# 2022-11-10.net
KiCad netlist of a schematic drawn in EasyEDA
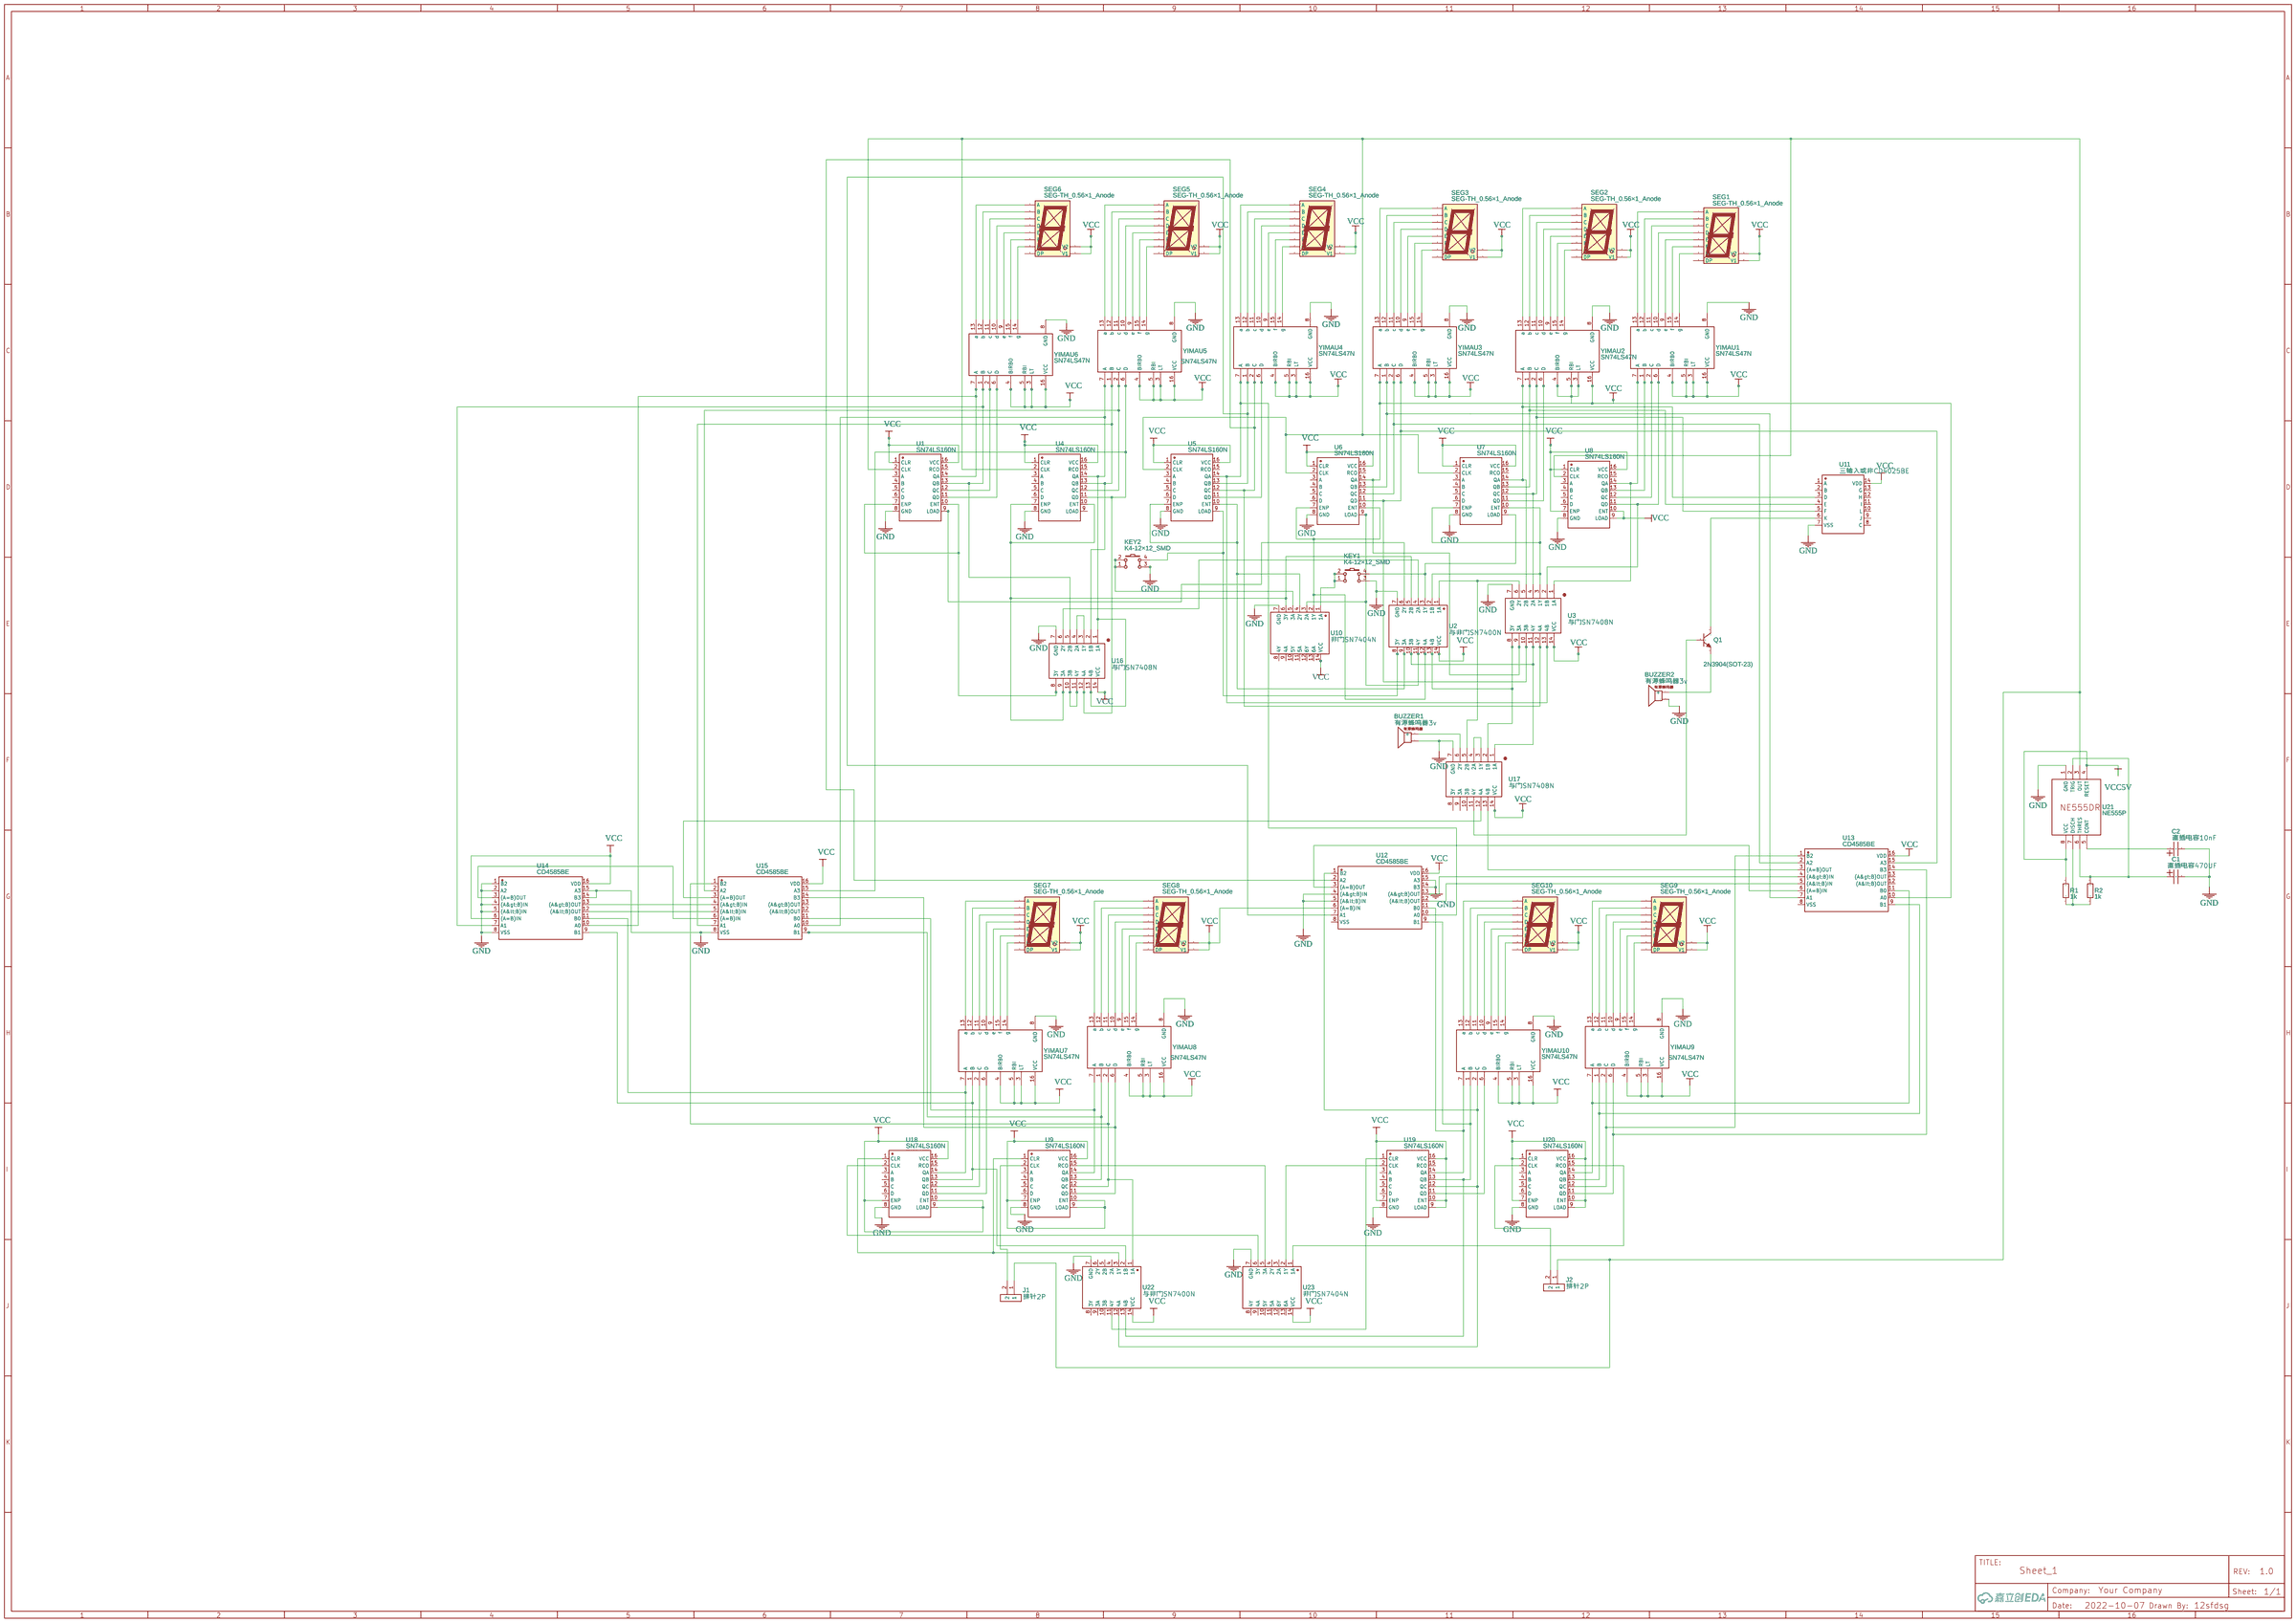
[diagram p0: schematic sheet]

(export (version "E")
  (design (tool "Eeschema 10.0.6"))
  (components
    (comp (ref "BUZZER1")
      (value "有源蜂鸣器3v")
      (fields (field (name "BOM_Manufacturer Part") "TMB12A12") (field (name "BOM_Supplier Part") "C96079"))
      (libsource (lib "") (part "有源蜂鸣器3v"))
    )
    (comp (ref "BUZZER2")
      (value "有源蜂鸣器3v")
      (fields (field (name "BOM_Manufacturer Part") "TMB12A12") (field (name "BOM_Supplier Part") "C96079"))
      (libsource (lib "") (part "有源蜂鸣器3v"))
    )
    (comp (ref "C1") (value "直插电容470UF") (libsource (lib "") (part "直插电容470UF_1")))
    (comp (ref "C2") (value "直插电容10nF") (libsource (lib "") (part "直插电容470UF")))
    (comp (ref "J1") (value "排针2P") (libsource (lib "") (part "排针2P")))
    (comp (ref "J2") (value "排针2P") (libsource (lib "") (part "排针2P")))
    (comp (ref "KEY1")
      (value "K4-12×12_SMD")
      (fields
        (field (name "BOM_Manufacturer Part") "K2-1103SP-E4SW-04")
        (field (name "BOM_Supplier Part") "C136697")
      )
      (libsource (lib "") (part "K4-12×12_SMD"))
    )
    (comp (ref "KEY2")
      (value "K4-12×12_SMD")
      (fields
        (field (name "BOM_Manufacturer Part") "K2-1103SP-E4SW-04")
        (field (name "BOM_Supplier Part") "C136697")
      )
      (libsource (lib "") (part "K4-12×12_SMD"))
    )
    (comp (ref "Q1")
      (value "2N3904(SOT-23)")
      (fields
        (field (name "BOM_Manufacturer Part") "2n3904S-RTK/PS")
        (field (name "BOM_Supplier Part") "C18536")
      )
      (libsource (lib "") (part "2N3904(SOT-23)"))
    )
    (comp (ref "R1")
      (value "1k")
      (fields
        (field (name "BOM_Manufacturer Part") "CFR0W4J0681A50")
        (field (name "BOM_Supplier Part") "C70784")
      )
      (libsource (lib "") (part "直插电阻"))
    )
    (comp (ref "R2")
      (value "1k")
      (fields
        (field (name "BOM_Manufacturer Part") "CFR0W4J0681A50")
        (field (name "BOM_Supplier Part") "C70784")
      )
      (libsource (lib "") (part "直插电阻"))
    )
    (comp (ref "SEG1")
      (value "SEG-TH_0.56×1_Anode")
      (fields (field (name "BOM_Supplier Part") "C8092"))
      (libsource (lib "") (part "SEG-TH_0.56×1_Anode"))
    )
    (comp (ref "SEG2")
      (value "SEG-TH_0.56×1_Anode")
      (fields (field (name "BOM_Supplier Part") "C8092"))
      (libsource (lib "") (part "SEG-TH_0.56×1_Anode"))
    )
    (comp (ref "SEG3")
      (value "SEG-TH_0.56×1_Anode")
      (fields (field (name "BOM_Supplier Part") "C8092"))
      (libsource (lib "") (part "SEG-TH_0.56×1_Anode"))
    )
    (comp (ref "SEG4")
      (value "SEG-TH_0.56×1_Anode")
      (fields (field (name "BOM_Supplier Part") "C8092"))
      (libsource (lib "") (part "SEG-TH_0.56×1_Anode"))
    )
    (comp (ref "SEG5")
      (value "SEG-TH_0.56×1_Anode")
      (fields (field (name "BOM_Supplier Part") "C8092"))
      (libsource (lib "") (part "SEG-TH_0.56×1_Anode"))
    )
    (comp (ref "SEG6")
      (value "SEG-TH_0.56×1_Anode")
      (fields (field (name "BOM_Supplier Part") "C8092"))
      (libsource (lib "") (part "SEG-TH_0.56×1_Anode"))
    )
    (comp (ref "SEG7")
      (value "SEG-TH_0.56×1_Anode")
      (fields (field (name "BOM_Supplier Part") "C8092"))
      (libsource (lib "") (part "SEG-TH_0.56×1_Anode"))
    )
    (comp (ref "SEG8")
      (value "SEG-TH_0.56×1_Anode")
      (fields (field (name "BOM_Supplier Part") "C8092"))
      (libsource (lib "") (part "SEG-TH_0.56×1_Anode"))
    )
    (comp (ref "SEG9")
      (value "SEG-TH_0.56×1_Anode")
      (fields (field (name "BOM_Supplier Part") "C8092"))
      (libsource (lib "") (part "SEG-TH_0.56×1_Anode"))
    )
    (comp (ref "SEG10")
      (value "SEG-TH_0.56×1_Anode")
      (fields (field (name "BOM_Supplier Part") "C8092"))
      (libsource (lib "") (part "SEG-TH_0.56×1_Anode"))
    )
    (comp (ref "U1")
      (value "SN74LS160N")
      (fields
        (field (name "BOM_Manufacturer Part") "CC0805JRNPO9BN821")
        (field (name "BOM_Supplier Part") "C113834")
      )
      (libsource (lib "") (part "SN74LS160N"))
    )
    (comp (ref "U2") (value "与非门SN7400N") (libsource (lib "") (part "SN7400N")))
    (comp (ref "U3") (value "与门SN7408N") (libsource (lib "") (part "SN7408N")))
    (comp (ref "U4")
      (value "SN74LS160N")
      (fields
        (field (name "BOM_Manufacturer Part") "CC0805JRNPO9BN821")
        (field (name "BOM_Supplier Part") "C113834")
      )
      (libsource (lib "") (part "SN74LS160N"))
    )
    (comp (ref "U5")
      (value "SN74LS160N")
      (fields
        (field (name "BOM_Manufacturer Part") "CC0805JRNPO9BN821")
        (field (name "BOM_Supplier Part") "C113834")
      )
      (libsource (lib "") (part "SN74LS160N"))
    )
    (comp (ref "U6")
      (value "SN74LS160N")
      (fields
        (field (name "BOM_Manufacturer Part") "CC0805JRNPO9BN821")
        (field (name "BOM_Supplier Part") "C113834")
      )
      (libsource (lib "") (part "SN74LS160N"))
    )
    (comp (ref "U7")
      (value "SN74LS160N")
      (fields
        (field (name "BOM_Manufacturer Part") "CC0805JRNPO9BN821")
        (field (name "BOM_Supplier Part") "C113834")
      )
      (libsource (lib "") (part "SN74LS160N"))
    )
    (comp (ref "U8")
      (value "SN74LS160N")
      (fields
        (field (name "BOM_Manufacturer Part") "CC0805JRNPO9BN821")
        (field (name "BOM_Supplier Part") "C113834")
      )
      (libsource (lib "") (part "SN74LS160N"))
    )
    (comp (ref "U9")
      (value "SN74LS160N")
      (fields
        (field (name "BOM_Manufacturer Part") "CC0805JRNPO9BN821")
        (field (name "BOM_Supplier Part") "C113834")
      )
      (libsource (lib "") (part "SN74LS160N"))
    )
    (comp (ref "U10") (value "非门SN7404N") (libsource (lib "") (part "SN7404N")))
    (comp (ref "U11")
      (value "三输入或非CD4025BE")
      (fields (field (name "BOM_Manufacturer Part") "CD4025BE") (field (name "BOM_Supplier Part") "C28214"))
      (libsource (lib "") (part "CD4025BE"))
    )
    (comp (ref "U12")
      (value "CD4585BE")
      (fields (field (name "BOM_Supplier Part") "C31466"))
      (libsource (lib "") (part "CD4585BE"))
    )
    (comp (ref "U13")
      (value "CD4585BE")
      (fields (field (name "BOM_Supplier Part") "C31466"))
      (libsource (lib "") (part "CD4585BE"))
    )
    (comp (ref "U14")
      (value "CD4585BE")
      (fields (field (name "BOM_Supplier Part") "C31466"))
      (libsource (lib "") (part "CD4585BE"))
    )
    (comp (ref "U15")
      (value "CD4585BE")
      (fields (field (name "BOM_Supplier Part") "C31466"))
      (libsource (lib "") (part "CD4585BE"))
    )
    (comp (ref "U16") (value "与门SN7408N") (libsource (lib "") (part "SN7408N")))
    (comp (ref "U17") (value "与门SN7408N") (libsource (lib "") (part "SN7408N")))
    (comp (ref "U18")
      (value "SN74LS160N")
      (fields
        (field (name "BOM_Manufacturer Part") "CC0805JRNPO9BN821")
        (field (name "BOM_Supplier Part") "C113834")
      )
      (libsource (lib "") (part "SN74LS160N"))
    )
    (comp (ref "U19")
      (value "SN74LS160N")
      (fields
        (field (name "BOM_Manufacturer Part") "CC0805JRNPO9BN821")
        (field (name "BOM_Supplier Part") "C113834")
      )
      (libsource (lib "") (part "SN74LS160N"))
    )
    (comp (ref "U20")
      (value "SN74LS160N")
      (fields
        (field (name "BOM_Manufacturer Part") "CC0805JRNPO9BN821")
        (field (name "BOM_Supplier Part") "C113834")
      )
      (libsource (lib "") (part "SN74LS160N"))
    )
    (comp (ref "U21") (value "NE555P") (libsource (lib "") (part "NE555P")))
    (comp (ref "U22") (value "与非门SN7400N") (libsource (lib "") (part "SN7400N")))
    (comp (ref "U23") (value "非门SN7404N") (libsource (lib "") (part "SN7404N")))
    (comp (ref "YIMAU1")
      (value "SN74LS47N")
      (fields (field (name "BOM_Supplier Part") "C129379"))
      (libsource (lib "") (part "Unknown_2395_-1825"))
    )
    (comp (ref "YIMAU2")
      (value "SN74LS47N")
      (fields (field (name "BOM_Supplier Part") "C129379"))
      (libsource (lib "") (part "Unknown_2230_-1820"))
    )
    (comp (ref "YIMAU3")
      (value "SN74LS47N")
      (fields (field (name "BOM_Supplier Part") "C129379"))
      (libsource (lib "") (part "Unknown_2025_-1825"))
    )
    (comp (ref "YIMAU4")
      (value "SN74LS47N")
      (fields (field (name "BOM_Supplier Part") "C129379"))
      (libsource (lib "") (part "Unknown_1825_-1825"))
    )
    (comp (ref "YIMAU5")
      (value "SN74LS47N")
      (fields (field (name "BOM_Supplier Part") "C129379"))
      (libsource (lib "") (part "Unknown_1630_-1820"))
    )
    (comp (ref "YIMAU6")
      (value "SN74LS47N")
      (fields (field (name "BOM_Supplier Part") "C129379"))
      (libsource (lib "") (part "Unknown_1445_-1815"))
    )
    (comp (ref "YIMAU7")
      (value "SN74LS47N")
      (fields (field (name "BOM_Supplier Part") "C129379"))
      (libsource (lib "") (part "Unknown_1430_-815"))
    )
    (comp (ref "YIMAU8")
      (value "SN74LS47N")
      (fields (field (name "BOM_Supplier Part") "C129379"))
      (libsource (lib "") (part "Unknown_1615_-820"))
    )
    (comp (ref "YIMAU9")
      (value "SN74LS47N")
      (fields (field (name "BOM_Supplier Part") "C129379"))
      (libsource (lib "") (part "Unknown_2330_-820"))
    )
    (comp (ref "YIMAU10")
      (value "SN74LS47N")
      (fields (field (name "BOM_Supplier Part") "C129379"))
      (libsource (lib "") (part "Unknown_2145_-815"))
    )
  )
  (nets
    (net (code "1") (name "GND") (class "Default")
      (node (ref "BUZZER1") (pin "-") (pinfunction "-_-") (pintype "unspecified"))
      (node (ref "BUZZER2") (pin "-") (pinfunction "-_-") (pintype "unspecified"))
      (node (ref "C1") (pin "2") (pinfunction "2_2") (pintype "unspecified"))
      (node (ref "C2") (pin "2") (pinfunction "2_2") (pintype "unspecified"))
      (node (ref "KEY1") (pin "3") (pinfunction "3_3") (pintype "unspecified"))
      (node (ref "KEY2") (pin "3") (pinfunction "3_3") (pintype "unspecified"))
      (node (ref "U1") (pin "8") (pinfunction "GND_8") (pintype "unspecified"))
      (node (ref "U10") (pin "7") (pinfunction "GND_7") (pintype "unspecified"))
      (node (ref "U11") (pin "7") (pinfunction "VSS_7") (pintype "unspecified"))
      (node (ref "U12") (pin "14") (pinfunction "B3_14") (pintype "unspecified"))
      (node (ref "U12") (pin "15") (pinfunction "A3_15") (pintype "unspecified"))
      (node (ref "U12") (pin "4") (pinfunction "(A&gt;B)IN_4") (pintype "unspecified"))
      (node (ref "U12") (pin "5") (pinfunction "(A&lt;B)IN_5") (pintype "unspecified"))
      (node (ref "U14") (pin "1") (pinfunction "B2_1") (pintype "unspecified"))
      (node (ref "U14") (pin "14") (pinfunction "B3_14") (pintype "unspecified"))
      (node (ref "U14") (pin "15") (pinfunction "A3_15") (pintype "unspecified"))
      (node (ref "U14") (pin "2") (pinfunction "A2_2") (pintype "unspecified"))
      (node (ref "U14") (pin "4") (pinfunction "(A&gt;B)IN_4") (pintype "unspecified"))
      (node (ref "U14") (pin "5") (pinfunction "(A&lt;B)IN_5") (pintype "unspecified"))
      (node (ref "U14") (pin "8") (pinfunction "VSS_8") (pintype "unspecified"))
      (node (ref "U15") (pin "8") (pinfunction "VSS_8") (pintype "unspecified"))
      (node (ref "U16") (pin "7") (pinfunction "GND_7") (pintype "unspecified"))
      (node (ref "U17") (pin "7") (pinfunction "GND_7") (pintype "unspecified"))
      (node (ref "U18") (pin "8") (pinfunction "GND_8") (pintype "unspecified"))
      (node (ref "U19") (pin "8") (pinfunction "GND_8") (pintype "unspecified"))
      (node (ref "U2") (pin "7") (pinfunction "GND_7") (pintype "unspecified"))
      (node (ref "U20") (pin "8") (pinfunction "GND_8") (pintype "unspecified"))
      (node (ref "U21") (pin "1") (pinfunction "GND_1") (pintype "unspecified"))
      (node (ref "U22") (pin "7") (pinfunction "GND_7") (pintype "unspecified"))
      (node (ref "U23") (pin "7") (pinfunction "GND_7") (pintype "unspecified"))
      (node (ref "U3") (pin "7") (pinfunction "GND_7") (pintype "unspecified"))
      (node (ref "U4") (pin "8") (pinfunction "GND_8") (pintype "unspecified"))
      (node (ref "U5") (pin "8") (pinfunction "GND_8") (pintype "unspecified"))
      (node (ref "U6") (pin "8") (pinfunction "GND_8") (pintype "unspecified"))
      (node (ref "U7") (pin "8") (pinfunction "GND_8") (pintype "unspecified"))
      (node (ref "U8") (pin "8") (pinfunction "GND_8") (pintype "unspecified"))
      (node (ref "U9") (pin "8") (pinfunction "GND_8") (pintype "unspecified"))
      (node (ref "YIMAU1") (pin "8") (pinfunction "GND_8") (pintype "passive"))
      (node (ref "YIMAU10") (pin "8") (pinfunction "GND_8") (pintype "passive"))
      (node (ref "YIMAU2") (pin "8") (pinfunction "GND_8") (pintype "passive"))
      (node (ref "YIMAU3") (pin "8") (pinfunction "GND_8") (pintype "passive"))
      (node (ref "YIMAU4") (pin "8") (pinfunction "GND_8") (pintype "passive"))
      (node (ref "YIMAU5") (pin "8") (pinfunction "GND_8") (pintype "passive"))
      (node (ref "YIMAU6") (pin "8") (pinfunction "GND_8") (pintype "passive"))
      (node (ref "YIMAU7") (pin "8") (pinfunction "GND_8") (pintype "passive"))
      (node (ref "YIMAU8") (pin "8") (pinfunction "GND_8") (pintype "passive"))
      (node (ref "YIMAU9") (pin "8") (pinfunction "GND_8") (pintype "passive"))
    )
    (net (code "2") (name "Net-(Q1-B)") (class "Default")
      (node (ref "Q1") (pin "2") (pinfunction "B_2") (pintype "input"))
      (node (ref "U17") (pin "11") (pinfunction "4Y_11") (pintype "unspecified"))
    )
    (net (code "3") (name "Net-(Q1-C)") (class "Default")
      (node (ref "Q1") (pin "3") (pinfunction "C_3") (pintype "input"))
      (node (ref "U11") (pin "6") (pinfunction "K_6") (pintype "unspecified"))
    )
    (net (code "4") (name "Net-(Q1-E)") (class "Default")
      (node (ref "BUZZER2") (pin "+") (pinfunction "+_+") (pintype "unspecified"))
      (node (ref "Q1") (pin "1") (pinfunction "E_1") (pintype "input"))
    )
    (net (code "5") (name "Net-(SEG1-A)") (class "Default")
      (node (ref "SEG1") (pin "7") (pinfunction "A_7") (pintype "unspecified"))
      (node (ref "YIMAU1") (pin "13") (pinfunction "a_13") (pintype "unspecified"))
    )
    (net (code "6") (name "Net-(SEG1-B)") (class "Default")
      (node (ref "SEG1") (pin "6") (pinfunction "B_6") (pintype "unspecified"))
      (node (ref "YIMAU1") (pin "12") (pinfunction "b_12") (pintype "unspecified"))
    )
    (net (code "7") (name "Net-(SEG1-C)") (class "Default")
      (node (ref "SEG1") (pin "4") (pinfunction "C_4") (pintype "unspecified"))
      (node (ref "YIMAU1") (pin "11") (pinfunction "c_11") (pintype "unspecified"))
    )
    (net (code "8") (name "Net-(SEG1-D)") (class "Default")
      (node (ref "SEG1") (pin "2") (pinfunction "D_2") (pintype "unspecified"))
      (node (ref "YIMAU1") (pin "10") (pinfunction "d_10") (pintype "unspecified"))
    )
    (net (code "9") (name "Net-(SEG1-E)") (class "Default")
      (node (ref "SEG1") (pin "1") (pinfunction "E_1") (pintype "unspecified"))
      (node (ref "YIMAU1") (pin "9") (pinfunction "e_9") (pintype "unspecified"))
    )
    (net (code "10") (name "Net-(SEG1-F)") (class "Default")
      (node (ref "SEG1") (pin "9") (pinfunction "F_9") (pintype "unspecified"))
      (node (ref "YIMAU1") (pin "15") (pinfunction "f_15") (pintype "unspecified"))
    )
    (net (code "11") (name "Net-(SEG1-G)") (class "Default")
      (node (ref "SEG1") (pin "10") (pinfunction "G_10") (pintype "unspecified"))
      (node (ref "YIMAU1") (pin "14") (pinfunction "g_14") (pintype "unspecified"))
    )
    (net (code "12") (name "Net-(SEG2-A)") (class "Default")
      (node (ref "SEG2") (pin "7") (pinfunction "A_7") (pintype "unspecified"))
      (node (ref "YIMAU2") (pin "13") (pinfunction "a_13") (pintype "unspecified"))
    )
    (net (code "13") (name "Net-(SEG2-B)") (class "Default")
      (node (ref "SEG2") (pin "6") (pinfunction "B_6") (pintype "unspecified"))
      (node (ref "YIMAU2") (pin "12") (pinfunction "b_12") (pintype "unspecified"))
    )
    (net (code "14") (name "Net-(SEG2-C)") (class "Default")
      (node (ref "SEG2") (pin "4") (pinfunction "C_4") (pintype "unspecified"))
      (node (ref "YIMAU2") (pin "11") (pinfunction "c_11") (pintype "unspecified"))
    )
    (net (code "15") (name "Net-(SEG2-D)") (class "Default")
      (node (ref "SEG2") (pin "2") (pinfunction "D_2") (pintype "unspecified"))
      (node (ref "YIMAU2") (pin "10") (pinfunction "d_10") (pintype "unspecified"))
    )
    (net (code "16") (name "Net-(SEG2-E)") (class "Default")
      (node (ref "SEG2") (pin "1") (pinfunction "E_1") (pintype "unspecified"))
      (node (ref "YIMAU2") (pin "9") (pinfunction "e_9") (pintype "unspecified"))
    )
    (net (code "17") (name "Net-(SEG2-F)") (class "Default")
      (node (ref "SEG2") (pin "9") (pinfunction "F_9") (pintype "unspecified"))
      (node (ref "YIMAU2") (pin "15") (pinfunction "f_15") (pintype "unspecified"))
    )
    (net (code "18") (name "Net-(SEG2-G)") (class "Default")
      (node (ref "SEG2") (pin "10") (pinfunction "G_10") (pintype "unspecified"))
      (node (ref "YIMAU2") (pin "14") (pinfunction "g_14") (pintype "unspecified"))
    )
    (net (code "19") (name "Net-(SEG3-A)") (class "Default")
      (node (ref "SEG3") (pin "7") (pinfunction "A_7") (pintype "unspecified"))
      (node (ref "YIMAU3") (pin "13") (pinfunction "a_13") (pintype "unspecified"))
    )
    (net (code "20") (name "Net-(SEG3-B)") (class "Default")
      (node (ref "SEG3") (pin "6") (pinfunction "B_6") (pintype "unspecified"))
      (node (ref "YIMAU3") (pin "12") (pinfunction "b_12") (pintype "unspecified"))
    )
    (net (code "21") (name "Net-(SEG3-C)") (class "Default")
      (node (ref "SEG3") (pin "4") (pinfunction "C_4") (pintype "unspecified"))
      (node (ref "YIMAU3") (pin "11") (pinfunction "c_11") (pintype "unspecified"))
    )
    (net (code "22") (name "Net-(SEG3-D)") (class "Default")
      (node (ref "SEG3") (pin "2") (pinfunction "D_2") (pintype "unspecified"))
      (node (ref "YIMAU3") (pin "10") (pinfunction "d_10") (pintype "unspecified"))
    )
    (net (code "23") (name "Net-(SEG3-E)") (class "Default")
      (node (ref "SEG3") (pin "1") (pinfunction "E_1") (pintype "unspecified"))
      (node (ref "YIMAU3") (pin "9") (pinfunction "e_9") (pintype "unspecified"))
    )
    (net (code "24") (name "Net-(SEG3-F)") (class "Default")
      (node (ref "SEG3") (pin "9") (pinfunction "F_9") (pintype "unspecified"))
      (node (ref "YIMAU3") (pin "15") (pinfunction "f_15") (pintype "unspecified"))
    )
    (net (code "25") (name "Net-(SEG3-G)") (class "Default")
      (node (ref "SEG3") (pin "10") (pinfunction "G_10") (pintype "unspecified"))
      (node (ref "YIMAU3") (pin "14") (pinfunction "g_14") (pintype "unspecified"))
    )
    (net (code "26") (name "Net-(SEG4-A)") (class "Default")
      (node (ref "SEG4") (pin "7") (pinfunction "A_7") (pintype "unspecified"))
      (node (ref "YIMAU4") (pin "13") (pinfunction "a_13") (pintype "unspecified"))
    )
    (net (code "27") (name "Net-(SEG4-B)") (class "Default")
      (node (ref "SEG4") (pin "6") (pinfunction "B_6") (pintype "unspecified"))
      (node (ref "YIMAU4") (pin "12") (pinfunction "b_12") (pintype "unspecified"))
    )
    (net (code "28") (name "Net-(SEG4-C)") (class "Default")
      (node (ref "SEG4") (pin "4") (pinfunction "C_4") (pintype "unspecified"))
      (node (ref "YIMAU4") (pin "11") (pinfunction "c_11") (pintype "unspecified"))
    )
    (net (code "29") (name "Net-(SEG4-D)") (class "Default")
      (node (ref "SEG4") (pin "2") (pinfunction "D_2") (pintype "unspecified"))
      (node (ref "YIMAU4") (pin "10") (pinfunction "d_10") (pintype "unspecified"))
    )
    (net (code "30") (name "Net-(SEG4-E)") (class "Default")
      (node (ref "SEG4") (pin "1") (pinfunction "E_1") (pintype "unspecified"))
      (node (ref "YIMAU4") (pin "9") (pinfunction "e_9") (pintype "unspecified"))
    )
    (net (code "31") (name "Net-(SEG4-F)") (class "Default")
      (node (ref "SEG4") (pin "9") (pinfunction "F_9") (pintype "unspecified"))
      (node (ref "YIMAU4") (pin "15") (pinfunction "f_15") (pintype "unspecified"))
    )
    (net (code "32") (name "Net-(SEG4-G)") (class "Default")
      (node (ref "SEG4") (pin "10") (pinfunction "G_10") (pintype "unspecified"))
      (node (ref "YIMAU4") (pin "14") (pinfunction "g_14") (pintype "unspecified"))
    )
    (net (code "33") (name "Net-(SEG5-A)") (class "Default")
      (node (ref "SEG5") (pin "7") (pinfunction "A_7") (pintype "unspecified"))
      (node (ref "YIMAU5") (pin "13") (pinfunction "a_13") (pintype "unspecified"))
    )
    (net (code "34") (name "Net-(SEG5-B)") (class "Default")
      (node (ref "SEG5") (pin "6") (pinfunction "B_6") (pintype "unspecified"))
      (node (ref "YIMAU5") (pin "12") (pinfunction "b_12") (pintype "unspecified"))
    )
    (net (code "35") (name "Net-(SEG5-C)") (class "Default")
      (node (ref "SEG5") (pin "4") (pinfunction "C_4") (pintype "unspecified"))
      (node (ref "YIMAU5") (pin "11") (pinfunction "c_11") (pintype "unspecified"))
    )
    (net (code "36") (name "Net-(SEG5-D)") (class "Default")
      (node (ref "SEG5") (pin "2") (pinfunction "D_2") (pintype "unspecified"))
      (node (ref "YIMAU5") (pin "10") (pinfunction "d_10") (pintype "unspecified"))
    )
    (net (code "37") (name "Net-(SEG5-E)") (class "Default")
      (node (ref "SEG5") (pin "1") (pinfunction "E_1") (pintype "unspecified"))
      (node (ref "YIMAU5") (pin "9") (pinfunction "e_9") (pintype "unspecified"))
    )
    (net (code "38") (name "Net-(SEG5-F)") (class "Default")
      (node (ref "SEG5") (pin "9") (pinfunction "F_9") (pintype "unspecified"))
      (node (ref "YIMAU5") (pin "15") (pinfunction "f_15") (pintype "unspecified"))
    )
    (net (code "39") (name "Net-(SEG5-G)") (class "Default")
      (node (ref "SEG5") (pin "10") (pinfunction "G_10") (pintype "unspecified"))
      (node (ref "YIMAU5") (pin "14") (pinfunction "g_14") (pintype "unspecified"))
    )
    (net (code "40") (name "Net-(SEG6-A)") (class "Default")
      (node (ref "SEG6") (pin "7") (pinfunction "A_7") (pintype "unspecified"))
      (node (ref "YIMAU6") (pin "13") (pinfunction "a_13") (pintype "unspecified"))
    )
    (net (code "41") (name "Net-(SEG6-B)") (class "Default")
      (node (ref "SEG6") (pin "6") (pinfunction "B_6") (pintype "unspecified"))
      (node (ref "YIMAU6") (pin "12") (pinfunction "b_12") (pintype "unspecified"))
    )
    (net (code "42") (name "Net-(SEG6-C)") (class "Default")
      (node (ref "SEG6") (pin "4") (pinfunction "C_4") (pintype "unspecified"))
      (node (ref "YIMAU6") (pin "11") (pinfunction "c_11") (pintype "unspecified"))
    )
    (net (code "43") (name "Net-(SEG6-D)") (class "Default")
      (node (ref "SEG6") (pin "2") (pinfunction "D_2") (pintype "unspecified"))
      (node (ref "YIMAU6") (pin "10") (pinfunction "d_10") (pintype "unspecified"))
    )
    (net (code "44") (name "Net-(SEG6-E)") (class "Default")
      (node (ref "SEG6") (pin "1") (pinfunction "E_1") (pintype "unspecified"))
      (node (ref "YIMAU6") (pin "9") (pinfunction "e_9") (pintype "unspecified"))
    )
    (net (code "45") (name "Net-(SEG6-F)") (class "Default")
      (node (ref "SEG6") (pin "9") (pinfunction "F_9") (pintype "unspecified"))
      (node (ref "YIMAU6") (pin "15") (pinfunction "f_15") (pintype "unspecified"))
    )
    (net (code "46") (name "Net-(SEG6-G)") (class "Default")
      (node (ref "SEG6") (pin "10") (pinfunction "G_10") (pintype "unspecified"))
      (node (ref "YIMAU6") (pin "14") (pinfunction "g_14") (pintype "unspecified"))
    )
    (net (code "47") (name "Net-(SEG7-A)") (class "Default")
      (node (ref "SEG7") (pin "7") (pinfunction "A_7") (pintype "unspecified"))
      (node (ref "YIMAU7") (pin "13") (pinfunction "a_13") (pintype "unspecified"))
    )
    (net (code "48") (name "Net-(SEG7-B)") (class "Default")
      (node (ref "SEG7") (pin "6") (pinfunction "B_6") (pintype "unspecified"))
      (node (ref "YIMAU7") (pin "12") (pinfunction "b_12") (pintype "unspecified"))
    )
    (net (code "49") (name "Net-(SEG7-C)") (class "Default")
      (node (ref "SEG7") (pin "4") (pinfunction "C_4") (pintype "unspecified"))
      (node (ref "YIMAU7") (pin "11") (pinfunction "c_11") (pintype "unspecified"))
    )
    (net (code "50") (name "Net-(SEG7-D)") (class "Default")
      (node (ref "SEG7") (pin "2") (pinfunction "D_2") (pintype "unspecified"))
      (node (ref "YIMAU7") (pin "10") (pinfunction "d_10") (pintype "unspecified"))
    )
    (net (code "51") (name "Net-(SEG7-E)") (class "Default")
      (node (ref "SEG7") (pin "1") (pinfunction "E_1") (pintype "unspecified"))
      (node (ref "YIMAU7") (pin "9") (pinfunction "e_9") (pintype "unspecified"))
    )
    (net (code "52") (name "Net-(SEG7-F)") (class "Default")
      (node (ref "SEG7") (pin "9") (pinfunction "F_9") (pintype "unspecified"))
      (node (ref "YIMAU7") (pin "15") (pinfunction "f_15") (pintype "unspecified"))
    )
    (net (code "53") (name "Net-(SEG7-G)") (class "Default")
      (node (ref "SEG7") (pin "10") (pinfunction "G_10") (pintype "unspecified"))
      (node (ref "YIMAU7") (pin "14") (pinfunction "g_14") (pintype "unspecified"))
    )
    (net (code "54") (name "Net-(SEG8-A)") (class "Default")
      (node (ref "SEG8") (pin "7") (pinfunction "A_7") (pintype "unspecified"))
      (node (ref "YIMAU8") (pin "13") (pinfunction "a_13") (pintype "unspecified"))
    )
    (net (code "55") (name "Net-(SEG8-B)") (class "Default")
      (node (ref "SEG8") (pin "6") (pinfunction "B_6") (pintype "unspecified"))
      (node (ref "YIMAU8") (pin "12") (pinfunction "b_12") (pintype "unspecified"))
    )
    (net (code "56") (name "Net-(SEG8-C)") (class "Default")
      (node (ref "SEG8") (pin "4") (pinfunction "C_4") (pintype "unspecified"))
      (node (ref "YIMAU8") (pin "11") (pinfunction "c_11") (pintype "unspecified"))
    )
    (net (code "57") (name "Net-(SEG8-D)") (class "Default")
      (node (ref "SEG8") (pin "2") (pinfunction "D_2") (pintype "unspecified"))
      (node (ref "YIMAU8") (pin "10") (pinfunction "d_10") (pintype "unspecified"))
    )
    (net (code "58") (name "Net-(SEG8-E)") (class "Default")
      (node (ref "SEG8") (pin "1") (pinfunction "E_1") (pintype "unspecified"))
      (node (ref "YIMAU8") (pin "9") (pinfunction "e_9") (pintype "unspecified"))
    )
    (net (code "59") (name "Net-(SEG8-F)") (class "Default")
      (node (ref "SEG8") (pin "9") (pinfunction "F_9") (pintype "unspecified"))
      (node (ref "YIMAU8") (pin "15") (pinfunction "f_15") (pintype "unspecified"))
    )
    (net (code "60") (name "Net-(SEG8-G)") (class "Default")
      (node (ref "SEG8") (pin "10") (pinfunction "G_10") (pintype "unspecified"))
      (node (ref "YIMAU8") (pin "14") (pinfunction "g_14") (pintype "unspecified"))
    )
    (net (code "61") (name "Net-(SEG9-A)") (class "Default")
      (node (ref "SEG9") (pin "7") (pinfunction "A_7") (pintype "unspecified"))
      (node (ref "YIMAU9") (pin "13") (pinfunction "a_13") (pintype "unspecified"))
    )
    (net (code "62") (name "Net-(SEG9-B)") (class "Default")
      (node (ref "SEG9") (pin "6") (pinfunction "B_6") (pintype "unspecified"))
      (node (ref "YIMAU9") (pin "12") (pinfunction "b_12") (pintype "unspecified"))
    )
    (net (code "63") (name "Net-(SEG9-C)") (class "Default")
      (node (ref "SEG9") (pin "4") (pinfunction "C_4") (pintype "unspecified"))
      (node (ref "YIMAU9") (pin "11") (pinfunction "c_11") (pintype "unspecified"))
    )
    (net (code "64") (name "Net-(SEG9-D)") (class "Default")
      (node (ref "SEG9") (pin "2") (pinfunction "D_2") (pintype "unspecified"))
      (node (ref "YIMAU9") (pin "10") (pinfunction "d_10") (pintype "unspecified"))
    )
    (net (code "65") (name "Net-(SEG9-E)") (class "Default")
      (node (ref "SEG9") (pin "1") (pinfunction "E_1") (pintype "unspecified"))
      (node (ref "YIMAU9") (pin "9") (pinfunction "e_9") (pintype "unspecified"))
    )
    (net (code "66") (name "Net-(SEG9-F)") (class "Default")
      (node (ref "SEG9") (pin "9") (pinfunction "F_9") (pintype "unspecified"))
      (node (ref "YIMAU9") (pin "15") (pinfunction "f_15") (pintype "unspecified"))
    )
    (net (code "67") (name "Net-(SEG9-G)") (class "Default")
      (node (ref "SEG9") (pin "10") (pinfunction "G_10") (pintype "unspecified"))
      (node (ref "YIMAU9") (pin "14") (pinfunction "g_14") (pintype "unspecified"))
    )
    (net (code "68") (name "Net-(SEG10-A)") (class "Default")
      (node (ref "SEG10") (pin "7") (pinfunction "A_7") (pintype "unspecified"))
      (node (ref "YIMAU10") (pin "13") (pinfunction "a_13") (pintype "unspecified"))
    )
    (net (code "69") (name "Net-(SEG10-B)") (class "Default")
      (node (ref "SEG10") (pin "6") (pinfunction "B_6") (pintype "unspecified"))
      (node (ref "YIMAU10") (pin "12") (pinfunction "b_12") (pintype "unspecified"))
    )
    (net (code "70") (name "Net-(SEG10-C)") (class "Default")
      (node (ref "SEG10") (pin "4") (pinfunction "C_4") (pintype "unspecified"))
      (node (ref "YIMAU10") (pin "11") (pinfunction "c_11") (pintype "unspecified"))
    )
    (net (code "71") (name "Net-(SEG10-D)") (class "Default")
      (node (ref "SEG10") (pin "2") (pinfunction "D_2") (pintype "unspecified"))
      (node (ref "YIMAU10") (pin "10") (pinfunction "d_10") (pintype "unspecified"))
    )
    (net (code "72") (name "Net-(SEG10-E)") (class "Default")
      (node (ref "SEG10") (pin "1") (pinfunction "E_1") (pintype "unspecified"))
      (node (ref "YIMAU10") (pin "9") (pinfunction "e_9") (pintype "unspecified"))
    )
    (net (code "73") (name "Net-(SEG10-F)") (class "Default")
      (node (ref "SEG10") (pin "9") (pinfunction "F_9") (pintype "unspecified"))
      (node (ref "YIMAU10") (pin "15") (pinfunction "f_15") (pintype "unspecified"))
    )
    (net (code "74") (name "Net-(SEG10-G)") (class "Default")
      (node (ref "SEG10") (pin "10") (pinfunction "G_10") (pintype "unspecified"))
      (node (ref "YIMAU10") (pin "14") (pinfunction "g_14") (pintype "unspecified"))
    )
    (net (code "75") (name "Net-(U1-CLK)") (class "Default")
      (node (ref "J1") (pin "1") (pinfunction "1_1") (pintype "unspecified"))
      (node (ref "J2") (pin "1") (pinfunction "1_1") (pintype "unspecified"))
      (node (ref "U1") (pin "2") (pinfunction "CLK_2") (pintype "unspecified"))
      (node (ref "U21") (pin "3") (pinfunction "OUT_3") (pintype "unspecified"))
      (node (ref "U4") (pin "2") (pinfunction "CLK_2") (pintype "unspecified"))
      (node (ref "U5") (pin "2") (pinfunction "CLK_2") (pintype "unspecified"))
      (node (ref "U6") (pin "2") (pinfunction "CLK_2") (pintype "unspecified"))
      (node (ref "U7") (pin "2") (pinfunction "CLK_2") (pintype "unspecified"))
      (node (ref "U8") (pin "2") (pinfunction "CLK_2") (pintype "unspecified"))
    )
    (net (code "76") (name "Net-(U1-ENP)") (class "Default")
      (node (ref "U1") (pin "10") (pinfunction "ENT_10") (pintype "unspecified"))
      (node (ref "U1") (pin "7") (pinfunction "ENP_7") (pintype "unspecified"))
      (node (ref "U16") (pin "8") (pinfunction "3Y_8") (pintype "unspecified"))
    )
    (net (code "77") (name "Net-(U1-LOAD)") (class "Default")
      (node (ref "U1") (pin "9") (pinfunction "LOAD_9") (pintype "unspecified"))
      (node (ref "U2") (pin "6") (pinfunction "2Y_6") (pintype "unspecified"))
    )
    (net (code "78") (name "Net-(U1-QA)") (class "Default")
      (node (ref "U1") (pin "14") (pinfunction "QA_14") (pintype "unspecified"))
      (node (ref "U14") (pin "10") (pinfunction "A0_10") (pintype "unspecified"))
      (node (ref "YIMAU6") (pin "7") (pinfunction "A_7") (pintype "unspecified"))
    )
    (net (code "79") (name "Net-(U1-QB)") (class "Default")
      (node (ref "U1") (pin "13") (pinfunction "QB_13") (pintype "unspecified"))
      (node (ref "U14") (pin "7") (pinfunction "A1_7") (pintype "unspecified"))
      (node (ref "U16") (pin "5") (pinfunction "2B_5") (pintype "unspecified"))
      (node (ref "YIMAU6") (pin "1") (pinfunction "B_1") (pintype "unspecified"))
    )
    (net (code "80") (name "Net-(U1-QC)") (class "Default")
      (node (ref "U1") (pin "12") (pinfunction "QC_12") (pintype "unspecified"))
      (node (ref "YIMAU6") (pin "2") (pinfunction "C_2") (pintype "unspecified"))
    )
    (net (code "81") (name "Net-(U1-QD)") (class "Default")
      (node (ref "U1") (pin "11") (pinfunction "QD_11") (pintype "unspecified"))
      (node (ref "YIMAU6") (pin "6") (pinfunction "D_6") (pintype "unspecified"))
    )
    (net (code "82") (name "Net-(U2-1B)") (class "Default")
      (node (ref "U2") (pin "2") (pinfunction "1B_2") (pintype "unspecified"))
      (node (ref "U3") (pin "3") (pinfunction "1Y_3") (pintype "unspecified"))
      (node (ref "U7") (pin "10") (pinfunction "ENT_10") (pintype "unspecified"))
      (node (ref "U7") (pin "7") (pinfunction "ENP_7") (pintype "unspecified"))
    )
    (net (code "83") (name "Net-(U2-1Y)") (class "Default")
      (node (ref "KEY1") (pin "4") (pinfunction "4_4") (pintype "unspecified"))
      (node (ref "U2") (pin "3") (pinfunction "1Y_3") (pintype "unspecified"))
      (node (ref "U7") (pin "9") (pinfunction "LOAD_9") (pintype "unspecified"))
    )
    (net (code "84") (name "Net-(U2-3Y)") (class "Default")
      (node (ref "KEY2") (pin "4") (pinfunction "4_4") (pintype "unspecified"))
      (node (ref "U2") (pin "8") (pinfunction "3Y_8") (pintype "unspecified"))
      (node (ref "U5") (pin "9") (pinfunction "LOAD_9") (pintype "unspecified"))
    )
    (net (code "85") (name "Net-(U3-1A)") (class "Default")
      (node (ref "U3") (pin "1") (pinfunction "1A_1") (pintype "unspecified"))
      (node (ref "U8") (pin "14") (pinfunction "QA_14") (pintype "unspecified"))
      (node (ref "YIMAU1") (pin "7") (pinfunction "A_7") (pintype "unspecified"))
    )
    (net (code "86") (name "Net-(U3-1B)") (class "Default")
      (node (ref "U3") (pin "2") (pinfunction "1B_2") (pintype "unspecified"))
      (node (ref "U8") (pin "11") (pinfunction "QD_11") (pintype "unspecified"))
      (node (ref "YIMAU1") (pin "6") (pinfunction "D_6") (pintype "unspecified"))
    )
    (net (code "87") (name "Net-(U5-QD)") (class "Default")
      (node (ref "U5") (pin "11") (pinfunction "QD_11") (pintype "unspecified"))
      (node (ref "YIMAU4") (pin "6") (pinfunction "D_6") (pintype "unspecified"))
    )
    (net (code "88") (name "Net-(U7-QD)") (class "Default")
      (node (ref "U7") (pin "11") (pinfunction "QD_11") (pintype "unspecified"))
      (node (ref "YIMAU2") (pin "6") (pinfunction "D_6") (pintype "unspecified"))
    )
    (net (code "89") (name "Net-(U8-QB)") (class "Default")
      (node (ref "U8") (pin "13") (pinfunction "QB_13") (pintype "unspecified"))
      (node (ref "YIMAU1") (pin "1") (pinfunction "B_1") (pintype "unspecified"))
    )
    (net (code "90") (name "Net-(U8-QC)") (class "Default")
      (node (ref "U8") (pin "12") (pinfunction "QC_12") (pintype "unspecified"))
      (node (ref "YIMAU1") (pin "2") (pinfunction "C_2") (pintype "unspecified"))
    )
    (net (code "91") (name "Net-(U9-CLK)") (class "Default")
      (node (ref "J1") (pin "2") (pinfunction "2_2") (pintype "unspecified"))
      (node (ref "U9") (pin "2") (pinfunction "CLK_2") (pintype "unspecified"))
    )
    (net (code "92") (name "Net-(U10-1A)") (class "Default")
      (node (ref "KEY1") (pin "1") (pinfunction "1_1") (pintype "unspecified"))
      (node (ref "KEY1") (pin "2") (pinfunction "2_2") (pintype "unspecified"))
      (node (ref "U10") (pin "1") (pinfunction "1A_1") (pintype "unspecified"))
    )
    (net (code "93") (name "Net-(U10-1Y)") (class "Default")
      (node (ref "U10") (pin "2") (pinfunction "1Y_2") (pintype "unspecified"))
      (node (ref "U2") (pin "12") (pinfunction "4A_12") (pintype "unspecified"))
      (node (ref "U6") (pin "10") (pinfunction "ENT_10") (pintype "unspecified"))
      (node (ref "U6") (pin "7") (pinfunction "ENP_7") (pintype "unspecified"))
    )
    (net (code "94") (name "Net-(U10-2A)") (class "Default")
      (node (ref "U10") (pin "3") (pinfunction "2A_3") (pintype "unspecified"))
      (node (ref "U2") (pin "11") (pinfunction "4Y_11") (pintype "unspecified"))
      (node (ref "U6") (pin "9") (pinfunction "LOAD_9") (pintype "unspecified"))
    )
    (net (code "95") (name "Net-(U10-2Y)") (class "Default")
      (node (ref "U10") (pin "4") (pinfunction "2Y_4") (pintype "unspecified"))
      (node (ref "U2") (pin "9") (pinfunction "3A_9") (pintype "unspecified"))
      (node (ref "U5") (pin "10") (pinfunction "ENT_10") (pintype "unspecified"))
      (node (ref "U5") (pin "7") (pinfunction "ENP_7") (pintype "unspecified"))
    )
    (net (code "96") (name "Net-(U10-3A)") (class "Default")
      (node (ref "KEY2") (pin "1") (pinfunction "1_1") (pintype "unspecified"))
      (node (ref "KEY2") (pin "2") (pinfunction "2_2") (pintype "unspecified"))
      (node (ref "U10") (pin "5") (pinfunction "3A_5") (pintype "unspecified"))
    )
    (net (code "97") (name "Net-(U10-3Y)") (class "Default")
      (node (ref "U10") (pin "6") (pinfunction "3Y_6") (pintype "unspecified"))
      (node (ref "U16") (pin "9") (pinfunction "3A_9") (pintype "unspecified"))
      (node (ref "U2") (pin "5") (pinfunction "2B_5") (pintype "unspecified"))
      (node (ref "U4") (pin "10") (pinfunction "ENT_10") (pintype "unspecified"))
      (node (ref "U4") (pin "7") (pinfunction "ENP_7") (pintype "unspecified"))
    )
    (net (code "98") (name "Net-(U11-D)") (class "Default")
      (node (ref "U11") (pin "3") (pinfunction "D_3") (pintype "unspecified"))
      (node (ref "U3") (pin "5") (pinfunction "2B_5") (pintype "unspecified"))
      (node (ref "U7") (pin "14") (pinfunction "QA_14") (pintype "unspecified"))
      (node (ref "YIMAU2") (pin "7") (pinfunction "A_7") (pintype "unspecified"))
    )
    (net (code "99") (name "Net-(U11-E)") (class "Default")
      (node (ref "U11") (pin "4") (pinfunction "E_4") (pintype "unspecified"))
      (node (ref "U7") (pin "13") (pinfunction "QB_13") (pintype "unspecified"))
      (node (ref "YIMAU2") (pin "1") (pinfunction "B_1") (pintype "unspecified"))
    )
    (net (code "100") (name "Net-(U11-F)") (class "Default")
      (node (ref "U11") (pin "5") (pinfunction "F_5") (pintype "unspecified"))
      (node (ref "U3") (pin "4") (pinfunction "2A_4") (pintype "unspecified"))
      (node (ref "U7") (pin "12") (pinfunction "QC_12") (pintype "unspecified"))
      (node (ref "YIMAU2") (pin "2") (pinfunction "C_2") (pintype "unspecified"))
    )
    (net (code "101") (name "Net-(U12-(A&gt;B)OUT)") (class "Default")
      (node (ref "U12") (pin "13") (pinfunction "(A&gt;B)OUT_13") (pintype "unspecified"))
      (node (ref "U13") (pin "4") (pinfunction "(A&gt;B)IN_4") (pintype "unspecified"))
    )
    (net (code "102") (name "Net-(U12-(A&lt;B)OUT)") (class "Default")
      (node (ref "U12") (pin "12") (pinfunction "(A&lt;B)OUT_12") (pintype "unspecified"))
      (node (ref "U13") (pin "5") (pinfunction "(A&lt;B)IN_5") (pintype "unspecified"))
    )
    (net (code "103") (name "Net-(U12-(A=B)OUT)") (class "Default")
      (node (ref "U12") (pin "3") (pinfunction "(A=B)OUT_3") (pintype "unspecified"))
      (node (ref "U13") (pin "6") (pinfunction "(A=B)IN_6") (pintype "unspecified"))
    )
    (net (code "104") (name "Net-(U12-A0)") (class "Default")
      (node (ref "U12") (pin "10") (pinfunction "A0_10") (pintype "unspecified"))
      (node (ref "U3") (pin "13") (pinfunction "4B_13") (pintype "unspecified"))
      (node (ref "U5") (pin "14") (pinfunction "QA_14") (pintype "unspecified"))
      (node (ref "YIMAU4") (pin "7") (pinfunction "A_7") (pintype "unspecified"))
    )
    (net (code "105") (name "Net-(U12-A1)") (class "Default")
      (node (ref "U12") (pin "7") (pinfunction "A1_7") (pintype "unspecified"))
      (node (ref "U5") (pin "13") (pinfunction "QB_13") (pintype "unspecified"))
      (node (ref "YIMAU4") (pin "1") (pinfunction "B_1") (pintype "unspecified"))
    )
    (net (code "106") (name "Net-(U12-A2)") (class "Default")
      (node (ref "U12") (pin "2") (pinfunction "A2_2") (pintype "unspecified"))
      (node (ref "U3") (pin "12") (pinfunction "4A_12") (pintype "unspecified"))
      (node (ref "U5") (pin "12") (pinfunction "QC_12") (pintype "unspecified"))
      (node (ref "YIMAU4") (pin "2") (pinfunction "C_2") (pintype "unspecified"))
    )
    (net (code "107") (name "Net-(U12-B0)") (class "Default")
      (node (ref "U12") (pin "11") (pinfunction "B0_11") (pintype "unspecified"))
      (node (ref "U19") (pin "14") (pinfunction "QA_14") (pintype "unspecified"))
      (node (ref "YIMAU10") (pin "7") (pinfunction "A_7") (pintype "unspecified"))
    )
    (net (code "108") (name "Net-(U12-B1)") (class "Default")
      (node (ref "U12") (pin "9") (pinfunction "B1_9") (pintype "unspecified"))
      (node (ref "U19") (pin "13") (pinfunction "QB_13") (pintype "unspecified"))
      (node (ref "U22") (pin "13") (pinfunction "4B_13") (pintype "unspecified"))
      (node (ref "YIMAU10") (pin "1") (pinfunction "B_1") (pintype "unspecified"))
    )
    (net (code "109") (name "Net-(U12-B2)") (class "Default")
      (node (ref "U12") (pin "1") (pinfunction "B2_1") (pintype "unspecified"))
      (node (ref "U19") (pin "12") (pinfunction "QC_12") (pintype "unspecified"))
      (node (ref "U22") (pin "12") (pinfunction "4A_12") (pintype "unspecified"))
      (node (ref "YIMAU10") (pin "2") (pinfunction "C_2") (pintype "unspecified"))
    )
    (net (code "110") (name "Net-(U13-(A=B)OUT)") (class "Default")
      (node (ref "U13") (pin "3") (pinfunction "(A=B)OUT_3") (pintype "unspecified"))
      (node (ref "U17") (pin "13") (pinfunction "4B_13") (pintype "unspecified"))
    )
    (net (code "111") (name "Net-(U13-A1)") (class "Default")
      (node (ref "U13") (pin "7") (pinfunction "A1_7") (pintype "unspecified"))
      (node (ref "U6") (pin "13") (pinfunction "QB_13") (pintype "unspecified"))
      (node (ref "YIMAU3") (pin "1") (pinfunction "B_1") (pintype "unspecified"))
    )
    (net (code "112") (name "Net-(U13-A2)") (class "Default")
      (node (ref "U13") (pin "2") (pinfunction "A2_2") (pintype "unspecified"))
      (node (ref "U6") (pin "12") (pinfunction "QC_12") (pintype "unspecified"))
      (node (ref "YIMAU3") (pin "2") (pinfunction "C_2") (pintype "unspecified"))
    )
    (net (code "113") (name "Net-(U13-A3)") (class "Default")
      (node (ref "U13") (pin "15") (pinfunction "A3_15") (pintype "unspecified"))
      (node (ref "U3") (pin "10") (pinfunction "3B_10") (pintype "unspecified"))
      (node (ref "U6") (pin "11") (pinfunction "QD_11") (pintype "unspecified"))
      (node (ref "YIMAU3") (pin "6") (pinfunction "D_6") (pintype "unspecified"))
    )
    (net (code "114") (name "Net-(U13-B0)") (class "Default")
      (node (ref "U13") (pin "11") (pinfunction "B0_11") (pintype "unspecified"))
      (node (ref "U20") (pin "14") (pinfunction "QA_14") (pintype "unspecified"))
      (node (ref "YIMAU9") (pin "7") (pinfunction "A_7") (pintype "unspecified"))
    )
    (net (code "115") (name "Net-(U13-B1)") (class "Default")
      (node (ref "U13") (pin "9") (pinfunction "B1_9") (pintype "unspecified"))
      (node (ref "U20") (pin "13") (pinfunction "QB_13") (pintype "unspecified"))
      (node (ref "YIMAU9") (pin "1") (pinfunction "B_1") (pintype "unspecified"))
    )
    (net (code "116") (name "Net-(U13-B2)") (class "Default")
      (node (ref "U13") (pin "1") (pinfunction "B2_1") (pintype "unspecified"))
      (node (ref "U20") (pin "12") (pinfunction "QC_12") (pintype "unspecified"))
      (node (ref "YIMAU9") (pin "2") (pinfunction "C_2") (pintype "unspecified"))
    )
    (net (code "117") (name "Net-(U13-B3)") (class "Default")
      (node (ref "U13") (pin "14") (pinfunction "B3_14") (pintype "unspecified"))
      (node (ref "U20") (pin "11") (pinfunction "QD_11") (pintype "unspecified"))
      (node (ref "YIMAU9") (pin "6") (pinfunction "D_6") (pintype "unspecified"))
    )
    (net (code "118") (name "Net-(U14-(A&gt;B)OUT)") (class "Default")
      (node (ref "U14") (pin "13") (pinfunction "(A&gt;B)OUT_13") (pintype "unspecified"))
      (node (ref "U15") (pin "4") (pinfunction "(A&gt;B)IN_4") (pintype "unspecified"))
    )
    (net (code "119") (name "Net-(U14-(A&lt;B)OUT)") (class "Default")
      (node (ref "U14") (pin "12") (pinfunction "(A&lt;B)OUT_12") (pintype "unspecified"))
      (node (ref "U15") (pin "5") (pinfunction "(A&lt;B)IN_5") (pintype "unspecified"))
    )
    (net (code "120") (name "Net-(U14-(A=B)OUT)") (class "Default")
      (node (ref "U14") (pin "3") (pinfunction "(A=B)OUT_3") (pintype "unspecified"))
      (node (ref "U15") (pin "6") (pinfunction "(A=B)IN_6") (pintype "unspecified"))
    )
    (net (code "121") (name "Net-(U14-B0)") (class "Default")
      (node (ref "U14") (pin "11") (pinfunction "B0_11") (pintype "unspecified"))
      (node (ref "U18") (pin "14") (pinfunction "QA_14") (pintype "unspecified"))
      (node (ref "YIMAU7") (pin "7") (pinfunction "A_7") (pintype "unspecified"))
    )
    (net (code "122") (name "Net-(U14-B1)") (class "Default")
      (node (ref "U14") (pin "9") (pinfunction "B1_9") (pintype "unspecified"))
      (node (ref "U18") (pin "13") (pinfunction "QB_13") (pintype "unspecified"))
      (node (ref "U22") (pin "2") (pinfunction "1B_2") (pintype "unspecified"))
      (node (ref "YIMAU7") (pin "1") (pinfunction "B_1") (pintype "unspecified"))
    )
    (net (code "123") (name "Net-(U15-(A=B)OUT)") (class "Default")
      (node (ref "U15") (pin "3") (pinfunction "(A=B)OUT_3") (pintype "unspecified"))
      (node (ref "U17") (pin "12") (pinfunction "4A_12") (pintype "unspecified"))
    )
    (net (code "124") (name "Net-(U15-A0)") (class "Default")
      (node (ref "U15") (pin "10") (pinfunction "A0_10") (pintype "unspecified"))
      (node (ref "U16") (pin "1") (pinfunction "1A_1") (pintype "unspecified"))
      (node (ref "U16") (pin "13") (pinfunction "4B_13") (pintype "unspecified"))
      (node (ref "U4") (pin "14") (pinfunction "QA_14") (pintype "unspecified"))
      (node (ref "YIMAU5") (pin "7") (pinfunction "A_7") (pintype "unspecified"))
    )
    (net (code "125") (name "Net-(U15-A1)") (class "Default")
      (node (ref "U15") (pin "7") (pinfunction "A1_7") (pintype "unspecified"))
      (node (ref "U16") (pin "2") (pinfunction "1B_2") (pintype "unspecified"))
      (node (ref "U4") (pin "13") (pinfunction "QB_13") (pintype "unspecified"))
      (node (ref "YIMAU5") (pin "1") (pinfunction "B_1") (pintype "unspecified"))
    )
    (net (code "126") (name "Net-(U15-A2)") (class "Default")
      (node (ref "U15") (pin "2") (pinfunction "A2_2") (pintype "unspecified"))
      (node (ref "U4") (pin "12") (pinfunction "QC_12") (pintype "unspecified"))
      (node (ref "YIMAU5") (pin "2") (pinfunction "C_2") (pintype "unspecified"))
    )
    (net (code "127") (name "Net-(U15-A3)") (class "Default")
      (node (ref "U15") (pin "15") (pinfunction "A3_15") (pintype "unspecified"))
      (node (ref "U16") (pin "12") (pinfunction "4A_12") (pintype "unspecified"))
      (node (ref "U4") (pin "11") (pinfunction "QD_11") (pintype "unspecified"))
      (node (ref "YIMAU5") (pin "6") (pinfunction "D_6") (pintype "unspecified"))
    )
    (net (code "128") (name "Net-(U15-B0)") (class "Default")
      (node (ref "U15") (pin "11") (pinfunction "B0_11") (pintype "unspecified"))
      (node (ref "U9") (pin "14") (pinfunction "QA_14") (pintype "unspecified"))
      (node (ref "YIMAU8") (pin "7") (pinfunction "A_7") (pintype "unspecified"))
    )
    (net (code "129") (name "Net-(U15-B1)") (class "Default")
      (node (ref "U15") (pin "9") (pinfunction "B1_9") (pintype "unspecified"))
      (node (ref "U9") (pin "13") (pinfunction "QB_13") (pintype "unspecified"))
      (node (ref "YIMAU8") (pin "1") (pinfunction "B_1") (pintype "unspecified"))
    )
    (net (code "130") (name "Net-(U15-B2)") (class "Default")
      (node (ref "U15") (pin "1") (pinfunction "B2_1") (pintype "unspecified"))
      (node (ref "U22") (pin "1") (pinfunction "1A_1") (pintype "unspecified"))
      (node (ref "U9") (pin "12") (pinfunction "QC_12") (pintype "unspecified"))
      (node (ref "YIMAU8") (pin "2") (pinfunction "C_2") (pintype "unspecified"))
    )
    (net (code "131") (name "Net-(U15-B3)") (class "Default")
      (node (ref "U15") (pin "14") (pinfunction "B3_14") (pintype "unspecified"))
      (node (ref "U9") (pin "11") (pinfunction "QD_11") (pintype "unspecified"))
      (node (ref "YIMAU8") (pin "6") (pinfunction "D_6") (pintype "unspecified"))
    )
    (net (code "132") (name "Net-(U16-1Y)") (class "Default")
      (node (ref "U16") (pin "3") (pinfunction "1Y_3") (pintype "unspecified"))
      (node (ref "U16") (pin "4") (pinfunction "2A_4") (pintype "unspecified"))
    )
    (net (code "133") (name "Net-(U16-2Y)") (class "Default")
      (node (ref "U16") (pin "6") (pinfunction "2Y_6") (pintype "unspecified"))
      (node (ref "U2") (pin "4") (pinfunction "2A_4") (pintype "unspecified"))
    )
    (net (code "134") (name "Net-(U16-3B)") (class "Default")
      (node (ref "U16") (pin "10") (pinfunction "3B_10") (pintype "unspecified"))
      (node (ref "U16") (pin "11") (pinfunction "4Y_11") (pintype "unspecified"))
    )
    (net (code "135") (name "Net-(U17-1A)") (class "Default")
      (node (ref "U17") (pin "1") (pinfunction "1A_1") (pintype "unspecified"))
      (node (ref "U2") (pin "10") (pinfunction "3B_10") (pintype "unspecified"))
      (node (ref "U3") (pin "11") (pinfunction "4Y_11") (pintype "unspecified"))
    )
    (net (code "136") (name "Net-(U17-1B)") (class "Default")
      (node (ref "U17") (pin "2") (pinfunction "1B_2") (pintype "unspecified"))
      (node (ref "U2") (pin "13") (pinfunction "4B_13") (pintype "unspecified"))
      (node (ref "U3") (pin "8") (pinfunction "3Y_8") (pintype "unspecified"))
    )
    (net (code "137") (name "Net-(U17-1Y)") (class "Default")
      (node (ref "U17") (pin "3") (pinfunction "1Y_3") (pintype "unspecified"))
      (node (ref "U17") (pin "4") (pinfunction "2A_4") (pintype "unspecified"))
    )
    (net (code "138") (name "Net-(U17-2B)") (class "Default")
      (node (ref "U17") (pin "5") (pinfunction "2B_5") (pintype "unspecified"))
      (node (ref "U2") (pin "1") (pinfunction "1A_1") (pintype "unspecified"))
      (node (ref "U3") (pin "6") (pinfunction "2Y_6") (pintype "unspecified"))
    )
    (net (code "139") (name "Net-(U17-2Y)") (class "Default")
      (node (ref "BUZZER1") (pin "+") (pinfunction "+_+") (pintype "unspecified"))
      (node (ref "U17") (pin "6") (pinfunction "2Y_6") (pintype "unspecified"))
    )
    (net (code "140") (name "Net-(U18-CLK)") (class "Default")
      (node (ref "U18") (pin "2") (pinfunction "CLK_2") (pintype "unspecified"))
      (node (ref "U23") (pin "6") (pinfunction "3Y_6") (pintype "unspecified"))
    )
    (net (code "141") (name "Net-(U18-CLR)") (class "Default")
      (node (ref "U18") (pin "1") (pinfunction "CLR_1") (pintype "unspecified"))
      (node (ref "U22") (pin "3") (pinfunction "1Y_3") (pintype "unspecified"))
      (node (ref "U9") (pin "1") (pinfunction "CLR_1") (pintype "unspecified"))
    )
    (net (code "142") (name "Net-(U18-QC)") (class "Default")
      (node (ref "U18") (pin "12") (pinfunction "QC_12") (pintype "unspecified"))
      (node (ref "YIMAU7") (pin "2") (pinfunction "C_2") (pintype "unspecified"))
    )
    (net (code "143") (name "Net-(U18-QD)") (class "Default")
      (node (ref "U18") (pin "11") (pinfunction "QD_11") (pintype "unspecified"))
      (node (ref "YIMAU7") (pin "6") (pinfunction "D_6") (pintype "unspecified"))
    )
    (net (code "144") (name "Net-(U19-CLK)") (class "Default")
      (node (ref "U19") (pin "2") (pinfunction "CLK_2") (pintype "unspecified"))
      (node (ref "U23") (pin "2") (pinfunction "1Y_2") (pintype "unspecified"))
    )
    (net (code "145") (name "Net-(U19-CLR)") (class "Default")
      (node (ref "U19") (pin "1") (pinfunction "CLR_1") (pintype "unspecified"))
      (node (ref "U22") (pin "11") (pinfunction "4Y_11") (pintype "unspecified"))
    )
    (net (code "146") (name "Net-(U19-QD)") (class "Default")
      (node (ref "U19") (pin "11") (pinfunction "QD_11") (pintype "unspecified"))
      (node (ref "YIMAU10") (pin "6") (pinfunction "D_6") (pintype "unspecified"))
    )
    (net (code "147") (name "Net-(U20-CLK)") (class "Default")
      (node (ref "J2") (pin "2") (pinfunction "2_2") (pintype "unspecified"))
      (node (ref "U20") (pin "2") (pinfunction "CLK_2") (pintype "unspecified"))
    )
    (net (code "148") (name "Net-(U20-RCO)") (class "Default")
      (node (ref "U20") (pin "15") (pinfunction "RCO_15") (pintype "unspecified"))
      (node (ref "U23") (pin "1") (pinfunction "1A_1") (pintype "unspecified"))
    )
    (net (code "149") (name "Net-(U21-CONT)") (class "Default")
      (node (ref "C2") (pin "1") (pinfunction "1_1") (pintype "unspecified"))
      (node (ref "U21") (pin "5") (pinfunction "CONT_5") (pintype "unspecified"))
    )
    (net (code "150") (name "Net-(U21-DISCH)") (class "Default")
      (node (ref "R1") (pin "1") (pinfunction "1_1") (pintype "input"))
      (node (ref "R2") (pin "1") (pinfunction "1_1") (pintype "input"))
      (node (ref "U21") (pin "7") (pinfunction "DISCH_7") (pintype "unspecified"))
    )
    (net (code "151") (name "Net-(U21-THRES)") (class "Default")
      (node (ref "C1") (pin "1") (pinfunction "1_1") (pintype "unspecified"))
      (node (ref "R2") (pin "2") (pinfunction "2_2") (pintype "input"))
      (node (ref "U21") (pin "2") (pinfunction "TRIG_2") (pintype "unspecified"))
      (node (ref "U21") (pin "6") (pinfunction "THRES_6") (pintype "unspecified"))
    )
    (net (code "152") (name "Net-(U23-3A)") (class "Default")
      (node (ref "U23") (pin "5") (pinfunction "3A_5") (pintype "unspecified"))
      (node (ref "U9") (pin "15") (pinfunction "RCO_15") (pintype "unspecified"))
    )
    (net (code "153") (name "VCC") (class "Default")
      (node (ref "SEG1") (pin "3") (pinfunction "V1_3") (pintype "unspecified"))
      (node (ref "SEG1") (pin "8") (pinfunction "V2_8") (pintype "unspecified"))
      (node (ref "SEG10") (pin "3") (pinfunction "V1_3") (pintype "unspecified"))
      (node (ref "SEG10") (pin "8") (pinfunction "V2_8") (pintype "unspecified"))
      (node (ref "SEG2") (pin "3") (pinfunction "V1_3") (pintype "unspecified"))
      (node (ref "SEG2") (pin "8") (pinfunction "V2_8") (pintype "unspecified"))
      (node (ref "SEG3") (pin "3") (pinfunction "V1_3") (pintype "unspecified"))
      (node (ref "SEG3") (pin "8") (pinfunction "V2_8") (pintype "unspecified"))
      (node (ref "SEG4") (pin "3") (pinfunction "V1_3") (pintype "unspecified"))
      (node (ref "SEG4") (pin "8") (pinfunction "V2_8") (pintype "unspecified"))
      (node (ref "SEG5") (pin "3") (pinfunction "V1_3") (pintype "unspecified"))
      (node (ref "SEG5") (pin "8") (pinfunction "V2_8") (pintype "unspecified"))
      (node (ref "SEG6") (pin "3") (pinfunction "V1_3") (pintype "unspecified"))
      (node (ref "SEG6") (pin "8") (pinfunction "V2_8") (pintype "unspecified"))
      (node (ref "SEG7") (pin "3") (pinfunction "V1_3") (pintype "unspecified"))
      (node (ref "SEG7") (pin "8") (pinfunction "V2_8") (pintype "unspecified"))
      (node (ref "SEG8") (pin "3") (pinfunction "V1_3") (pintype "unspecified"))
      (node (ref "SEG8") (pin "8") (pinfunction "V2_8") (pintype "unspecified"))
      (node (ref "SEG9") (pin "3") (pinfunction "V1_3") (pintype "unspecified"))
      (node (ref "SEG9") (pin "8") (pinfunction "V2_8") (pintype "unspecified"))
      (node (ref "U1") (pin "1") (pinfunction "CLR_1") (pintype "unspecified"))
      (node (ref "U1") (pin "16") (pinfunction "VCC_16") (pintype "unspecified"))
      (node (ref "U10") (pin "14") (pinfunction "VCC_14") (pintype "unspecified"))
      (node (ref "U11") (pin "14") (pinfunction "VDD_14") (pintype "unspecified"))
      (node (ref "U12") (pin "16") (pinfunction "VDD_16") (pintype "unspecified"))
      (node (ref "U12") (pin "6") (pinfunction "(A=B)IN_6") (pintype "unspecified"))
      (node (ref "U13") (pin "10") (pinfunction "A0_10") (pintype "unspecified"))
      (node (ref "U13") (pin "16") (pinfunction "VDD_16") (pintype "unspecified"))
      (node (ref "U14") (pin "16") (pinfunction "VDD_16") (pintype "unspecified"))
      (node (ref "U14") (pin "6") (pinfunction "(A=B)IN_6") (pintype "unspecified"))
      (node (ref "U15") (pin "16") (pinfunction "VDD_16") (pintype "unspecified"))
      (node (ref "U16") (pin "14") (pinfunction "VCC_14") (pintype "unspecified"))
      (node (ref "U17") (pin "14") (pinfunction "VCC_14") (pintype "unspecified"))
      (node (ref "U18") (pin "10") (pinfunction "ENT_10") (pintype "unspecified"))
      (node (ref "U18") (pin "16") (pinfunction "VCC_16") (pintype "unspecified"))
      (node (ref "U18") (pin "7") (pinfunction "ENP_7") (pintype "unspecified"))
      (node (ref "U18") (pin "9") (pinfunction "LOAD_9") (pintype "unspecified"))
      (node (ref "U19") (pin "10") (pinfunction "ENT_10") (pintype "unspecified"))
      (node (ref "U19") (pin "16") (pinfunction "VCC_16") (pintype "unspecified"))
      (node (ref "U19") (pin "7") (pinfunction "ENP_7") (pintype "unspecified"))
      (node (ref "U19") (pin "9") (pinfunction "LOAD_9") (pintype "unspecified"))
      (node (ref "U2") (pin "14") (pinfunction "VCC_14") (pintype "unspecified"))
      (node (ref "U20") (pin "1") (pinfunction "CLR_1") (pintype "unspecified"))
      (node (ref "U20") (pin "10") (pinfunction "ENT_10") (pintype "unspecified"))
      (node (ref "U20") (pin "16") (pinfunction "VCC_16") (pintype "unspecified"))
      (node (ref "U20") (pin "7") (pinfunction "ENP_7") (pintype "unspecified"))
      (node (ref "U20") (pin "9") (pinfunction "LOAD_9") (pintype "unspecified"))
      (node (ref "U22") (pin "14") (pinfunction "VCC_14") (pintype "unspecified"))
      (node (ref "U23") (pin "14") (pinfunction "VCC_14") (pintype "unspecified"))
      (node (ref "U3") (pin "14") (pinfunction "VCC_14") (pintype "unspecified"))
      (node (ref "U3") (pin "9") (pinfunction "3A_9") (pintype "unspecified"))
      (node (ref "U4") (pin "1") (pinfunction "CLR_1") (pintype "unspecified"))
      (node (ref "U4") (pin "16") (pinfunction "VCC_16") (pintype "unspecified"))
      (node (ref "U5") (pin "1") (pinfunction "CLR_1") (pintype "unspecified"))
      (node (ref "U5") (pin "16") (pinfunction "VCC_16") (pintype "unspecified"))
      (node (ref "U6") (pin "1") (pinfunction "CLR_1") (pintype "unspecified"))
      (node (ref "U6") (pin "14") (pinfunction "QA_14") (pintype "unspecified"))
      (node (ref "U6") (pin "16") (pinfunction "VCC_16") (pintype "unspecified"))
      (node (ref "U7") (pin "1") (pinfunction "CLR_1") (pintype "unspecified"))
      (node (ref "U7") (pin "16") (pinfunction "VCC_16") (pintype "unspecified"))
      (node (ref "U8") (pin "1") (pinfunction "CLR_1") (pintype "unspecified"))
      (node (ref "U8") (pin "10") (pinfunction "ENT_10") (pintype "unspecified"))
      (node (ref "U8") (pin "16") (pinfunction "VCC_16") (pintype "unspecified"))
      (node (ref "U8") (pin "7") (pinfunction "ENP_7") (pintype "unspecified"))
      (node (ref "U8") (pin "9") (pinfunction "LOAD_9") (pintype "unspecified"))
      (node (ref "U9") (pin "10") (pinfunction "ENT_10") (pintype "unspecified"))
      (node (ref "U9") (pin "16") (pinfunction "VCC_16") (pintype "unspecified"))
      (node (ref "U9") (pin "7") (pinfunction "ENP_7") (pintype "unspecified"))
      (node (ref "U9") (pin "9") (pinfunction "LOAD_9") (pintype "unspecified"))
      (node (ref "YIMAU1") (pin "16") (pinfunction "VCC_16") (pintype "passive"))
      (node (ref "YIMAU1") (pin "3") (pinfunction "LT_3") (pintype "unspecified"))
      (node (ref "YIMAU1") (pin "4") (pinfunction "BIRBO_4") (pintype "bidirectional"))
      (node (ref "YIMAU1") (pin "5") (pinfunction "RBI_5") (pintype "unspecified"))
      (node (ref "YIMAU10") (pin "16") (pinfunction "VCC_16") (pintype "passive"))
      (node (ref "YIMAU10") (pin "3") (pinfunction "LT_3") (pintype "unspecified"))
      (node (ref "YIMAU10") (pin "4") (pinfunction "BIRBO_4") (pintype "bidirectional"))
      (node (ref "YIMAU10") (pin "5") (pinfunction "RBI_5") (pintype "unspecified"))
      (node (ref "YIMAU2") (pin "16") (pinfunction "VCC_16") (pintype "passive"))
      (node (ref "YIMAU2") (pin "3") (pinfunction "LT_3") (pintype "unspecified"))
      (node (ref "YIMAU2") (pin "4") (pinfunction "BIRBO_4") (pintype "bidirectional"))
      (node (ref "YIMAU2") (pin "5") (pinfunction "RBI_5") (pintype "unspecified"))
      (node (ref "YIMAU3") (pin "16") (pinfunction "VCC_16") (pintype "passive"))
      (node (ref "YIMAU3") (pin "3") (pinfunction "LT_3") (pintype "unspecified"))
      (node (ref "YIMAU3") (pin "4") (pinfunction "BIRBO_4") (pintype "bidirectional"))
      (node (ref "YIMAU3") (pin "5") (pinfunction "RBI_5") (pintype "unspecified"))
      (node (ref "YIMAU3") (pin "7") (pinfunction "A_7") (pintype "unspecified"))
      (node (ref "YIMAU4") (pin "16") (pinfunction "VCC_16") (pintype "passive"))
      (node (ref "YIMAU4") (pin "3") (pinfunction "LT_3") (pintype "unspecified"))
      (node (ref "YIMAU4") (pin "4") (pinfunction "BIRBO_4") (pintype "bidirectional"))
      (node (ref "YIMAU4") (pin "5") (pinfunction "RBI_5") (pintype "unspecified"))
      (node (ref "YIMAU5") (pin "16") (pinfunction "VCC_16") (pintype "passive"))
      (node (ref "YIMAU5") (pin "3") (pinfunction "LT_3") (pintype "unspecified"))
      (node (ref "YIMAU5") (pin "4") (pinfunction "BIRBO_4") (pintype "bidirectional"))
      (node (ref "YIMAU5") (pin "5") (pinfunction "RBI_5") (pintype "unspecified"))
      (node (ref "YIMAU6") (pin "16") (pinfunction "VCC_16") (pintype "passive"))
      (node (ref "YIMAU6") (pin "3") (pinfunction "LT_3") (pintype "unspecified"))
      (node (ref "YIMAU6") (pin "4") (pinfunction "BIRBO_4") (pintype "bidirectional"))
      (node (ref "YIMAU6") (pin "5") (pinfunction "RBI_5") (pintype "unspecified"))
      (node (ref "YIMAU7") (pin "16") (pinfunction "VCC_16") (pintype "passive"))
      (node (ref "YIMAU7") (pin "3") (pinfunction "LT_3") (pintype "unspecified"))
      (node (ref "YIMAU7") (pin "4") (pinfunction "BIRBO_4") (pintype "bidirectional"))
      (node (ref "YIMAU7") (pin "5") (pinfunction "RBI_5") (pintype "unspecified"))
      (node (ref "YIMAU8") (pin "16") (pinfunction "VCC_16") (pintype "passive"))
      (node (ref "YIMAU8") (pin "3") (pinfunction "LT_3") (pintype "unspecified"))
      (node (ref "YIMAU8") (pin "4") (pinfunction "BIRBO_4") (pintype "bidirectional"))
      (node (ref "YIMAU8") (pin "5") (pinfunction "RBI_5") (pintype "unspecified"))
      (node (ref "YIMAU9") (pin "16") (pinfunction "VCC_16") (pintype "passive"))
      (node (ref "YIMAU9") (pin "3") (pinfunction "LT_3") (pintype "unspecified"))
      (node (ref "YIMAU9") (pin "4") (pinfunction "BIRBO_4") (pintype "bidirectional"))
      (node (ref "YIMAU9") (pin "5") (pinfunction "RBI_5") (pintype "unspecified"))
    )
    (net (code "154") (name "VCC5V") (class "Default")
      (node (ref "R1") (pin "2") (pinfunction "2_2") (pintype "input"))
      (node (ref "U21") (pin "4") (pinfunction "RESET_4") (pintype "unspecified"))
      (node (ref "U21") (pin "8") (pinfunction "VCC_8") (pintype "unspecified"))
    )
    (net (code "155") (name "unconnected-(SEG1-DP-Pad5)") (class "Default")
      (node (ref "SEG1") (pin "5") (pinfunction "DP_5") (pintype "unspecified"))
    )
    (net (code "156") (name "unconnected-(SEG2-DP-Pad5)") (class "Default")
      (node (ref "SEG2") (pin "5") (pinfunction "DP_5") (pintype "unspecified"))
    )
    (net (code "157") (name "unconnected-(SEG3-DP-Pad5)") (class "Default")
      (node (ref "SEG3") (pin "5") (pinfunction "DP_5") (pintype "unspecified"))
    )
    (net (code "158") (name "unconnected-(SEG4-DP-Pad5)") (class "Default")
      (node (ref "SEG4") (pin "5") (pinfunction "DP_5") (pintype "unspecified"))
    )
    (net (code "159") (name "unconnected-(SEG5-DP-Pad5)") (class "Default")
      (node (ref "SEG5") (pin "5") (pinfunction "DP_5") (pintype "unspecified"))
    )
    (net (code "160") (name "unconnected-(SEG6-DP-Pad5)") (class "Default")
      (node (ref "SEG6") (pin "5") (pinfunction "DP_5") (pintype "unspecified"))
    )
    (net (code "161") (name "unconnected-(SEG7-DP-Pad5)") (class "Default")
      (node (ref "SEG7") (pin "5") (pinfunction "DP_5") (pintype "unspecified"))
    )
    (net (code "162") (name "unconnected-(SEG8-DP-Pad5)") (class "Default")
      (node (ref "SEG8") (pin "5") (pinfunction "DP_5") (pintype "unspecified"))
    )
    (net (code "163") (name "unconnected-(SEG9-DP-Pad5)") (class "Default")
      (node (ref "SEG9") (pin "5") (pinfunction "DP_5") (pintype "unspecified"))
    )
    (net (code "164") (name "unconnected-(SEG10-DP-Pad5)") (class "Default")
      (node (ref "SEG10") (pin "5") (pinfunction "DP_5") (pintype "unspecified"))
    )
    (net (code "165") (name "unconnected-(U1-A-Pad3)") (class "Default")
      (node (ref "U1") (pin "3") (pinfunction "A_3") (pintype "unspecified"))
    )
    (net (code "166") (name "unconnected-(U1-B-Pad4)") (class "Default")
      (node (ref "U1") (pin "4") (pinfunction "B_4") (pintype "unspecified"))
    )
    (net (code "167") (name "unconnected-(U1-C-Pad5)") (class "Default")
      (node (ref "U1") (pin "5") (pinfunction "C_5") (pintype "unspecified"))
    )
    (net (code "168") (name "unconnected-(U1-D-Pad6)") (class "Default")
      (node (ref "U1") (pin "6") (pinfunction "D_6") (pintype "unspecified"))
    )
    (net (code "169") (name "unconnected-(U1-RCO-Pad15)") (class "Default")
      (node (ref "U1") (pin "15") (pinfunction "RCO_15") (pintype "unspecified"))
    )
    (net (code "170") (name "unconnected-(U4-A-Pad3)") (class "Default")
      (node (ref "U4") (pin "3") (pinfunction "A_3") (pintype "unspecified"))
    )
    (net (code "171") (name "unconnected-(U4-B-Pad4)") (class "Default")
      (node (ref "U4") (pin "4") (pinfunction "B_4") (pintype "unspecified"))
    )
    (net (code "172") (name "unconnected-(U4-C-Pad5)") (class "Default")
      (node (ref "U4") (pin "5") (pinfunction "C_5") (pintype "unspecified"))
    )
    (net (code "173") (name "unconnected-(U4-D-Pad6)") (class "Default")
      (node (ref "U4") (pin "6") (pinfunction "D_6") (pintype "unspecified"))
    )
    (net (code "174") (name "unconnected-(U4-LOAD-Pad9)") (class "Default")
      (node (ref "U4") (pin "9") (pinfunction "LOAD_9") (pintype "unspecified"))
    )
    (net (code "175") (name "unconnected-(U4-RCO-Pad15)") (class "Default")
      (node (ref "U4") (pin "15") (pinfunction "RCO_15") (pintype "unspecified"))
    )
    (net (code "176") (name "unconnected-(U5-A-Pad3)") (class "Default")
      (node (ref "U5") (pin "3") (pinfunction "A_3") (pintype "unspecified"))
    )
    (net (code "177") (name "unconnected-(U5-B-Pad4)") (class "Default")
      (node (ref "U5") (pin "4") (pinfunction "B_4") (pintype "unspecified"))
    )
    (net (code "178") (name "unconnected-(U5-C-Pad5)") (class "Default")
      (node (ref "U5") (pin "5") (pinfunction "C_5") (pintype "unspecified"))
    )
    (net (code "179") (name "unconnected-(U5-D-Pad6)") (class "Default")
      (node (ref "U5") (pin "6") (pinfunction "D_6") (pintype "unspecified"))
    )
    (net (code "180") (name "unconnected-(U5-RCO-Pad15)") (class "Default")
      (node (ref "U5") (pin "15") (pinfunction "RCO_15") (pintype "unspecified"))
    )
    (net (code "181") (name "unconnected-(U6-A-Pad3)") (class "Default")
      (node (ref "U6") (pin "3") (pinfunction "A_3") (pintype "unspecified"))
    )
    (net (code "182") (name "unconnected-(U6-B-Pad4)") (class "Default")
      (node (ref "U6") (pin "4") (pinfunction "B_4") (pintype "unspecified"))
    )
    (net (code "183") (name "unconnected-(U6-C-Pad5)") (class "Default")
      (node (ref "U6") (pin "5") (pinfunction "C_5") (pintype "unspecified"))
    )
    (net (code "184") (name "unconnected-(U6-D-Pad6)") (class "Default")
      (node (ref "U6") (pin "6") (pinfunction "D_6") (pintype "unspecified"))
    )
    (net (code "185") (name "unconnected-(U6-RCO-Pad15)") (class "Default")
      (node (ref "U6") (pin "15") (pinfunction "RCO_15") (pintype "unspecified"))
    )
    (net (code "186") (name "unconnected-(U7-A-Pad3)") (class "Default")
      (node (ref "U7") (pin "3") (pinfunction "A_3") (pintype "unspecified"))
    )
    (net (code "187") (name "unconnected-(U7-B-Pad4)") (class "Default")
      (node (ref "U7") (pin "4") (pinfunction "B_4") (pintype "unspecified"))
    )
    (net (code "188") (name "unconnected-(U7-C-Pad5)") (class "Default")
      (node (ref "U7") (pin "5") (pinfunction "C_5") (pintype "unspecified"))
    )
    (net (code "189") (name "unconnected-(U7-D-Pad6)") (class "Default")
      (node (ref "U7") (pin "6") (pinfunction "D_6") (pintype "unspecified"))
    )
    (net (code "190") (name "unconnected-(U7-RCO-Pad15)") (class "Default")
      (node (ref "U7") (pin "15") (pinfunction "RCO_15") (pintype "unspecified"))
    )
    (net (code "191") (name "unconnected-(U8-A-Pad3)") (class "Default")
      (node (ref "U8") (pin "3") (pinfunction "A_3") (pintype "unspecified"))
    )
    (net (code "192") (name "unconnected-(U8-B-Pad4)") (class "Default")
      (node (ref "U8") (pin "4") (pinfunction "B_4") (pintype "unspecified"))
    )
    (net (code "193") (name "unconnected-(U8-C-Pad5)") (class "Default")
      (node (ref "U8") (pin "5") (pinfunction "C_5") (pintype "unspecified"))
    )
    (net (code "194") (name "unconnected-(U8-D-Pad6)") (class "Default")
      (node (ref "U8") (pin "6") (pinfunction "D_6") (pintype "unspecified"))
    )
    (net (code "195") (name "unconnected-(U8-RCO-Pad15)") (class "Default")
      (node (ref "U8") (pin "15") (pinfunction "RCO_15") (pintype "unspecified"))
    )
    (net (code "196") (name "unconnected-(U9-A-Pad3)") (class "Default")
      (node (ref "U9") (pin "3") (pinfunction "A_3") (pintype "unspecified"))
    )
    (net (code "197") (name "unconnected-(U9-B-Pad4)") (class "Default")
      (node (ref "U9") (pin "4") (pinfunction "B_4") (pintype "unspecified"))
    )
    (net (code "198") (name "unconnected-(U9-C-Pad5)") (class "Default")
      (node (ref "U9") (pin "5") (pinfunction "C_5") (pintype "unspecified"))
    )
    (net (code "199") (name "unconnected-(U9-D-Pad6)") (class "Default")
      (node (ref "U9") (pin "6") (pinfunction "D_6") (pintype "unspecified"))
    )
    (net (code "200") (name "unconnected-(U10-4A-Pad9)") (class "Default")
      (node (ref "U10") (pin "9") (pinfunction "4A_9") (pintype "unspecified"))
    )
    (net (code "201") (name "unconnected-(U10-4Y-Pad8)") (class "Default")
      (node (ref "U10") (pin "8") (pinfunction "4Y_8") (pintype "unspecified"))
    )
    (net (code "202") (name "unconnected-(U10-5A-Pad11)") (class "Default")
      (node (ref "U10") (pin "11") (pinfunction "5A_11") (pintype "unspecified"))
    )
    (net (code "203") (name "unconnected-(U10-5Y-Pad10)") (class "Default")
      (node (ref "U10") (pin "10") (pinfunction "5Y_10") (pintype "unspecified"))
    )
    (net (code "204") (name "unconnected-(U10-6A-Pad13)") (class "Default")
      (node (ref "U10") (pin "13") (pinfunction "6A_13") (pintype "unspecified"))
    )
    (net (code "205") (name "unconnected-(U10-6Y-Pad12)") (class "Default")
      (node (ref "U10") (pin "12") (pinfunction "6Y_12") (pintype "unspecified"))
    )
    (net (code "206") (name "unconnected-(U11-A-Pad1)") (class "Default")
      (node (ref "U11") (pin "1") (pinfunction "A_1") (pintype "unspecified"))
    )
    (net (code "207") (name "unconnected-(U11-B-Pad2)") (class "Default")
      (node (ref "U11") (pin "2") (pinfunction "B_2") (pintype "unspecified"))
    )
    (net (code "208") (name "unconnected-(U11-C-Pad8)") (class "Default")
      (node (ref "U11") (pin "8") (pinfunction "C_8") (pintype "unspecified"))
    )
    (net (code "209") (name "unconnected-(U11-G-Pad13)") (class "Default")
      (node (ref "U11") (pin "13") (pinfunction "G_13") (pintype "unspecified"))
    )
    (net (code "210") (name "unconnected-(U11-H-Pad12)") (class "Default")
      (node (ref "U11") (pin "12") (pinfunction "H_12") (pintype "unspecified"))
    )
    (net (code "211") (name "unconnected-(U11-I-Pad11)") (class "Default")
      (node (ref "U11") (pin "11") (pinfunction "I_11") (pintype "unspecified"))
    )
    (net (code "212") (name "unconnected-(U11-J-Pad9)") (class "Default")
      (node (ref "U11") (pin "9") (pinfunction "J_9") (pintype "unspecified"))
    )
    (net (code "213") (name "unconnected-(U11-L-Pad10)") (class "Default")
      (node (ref "U11") (pin "10") (pinfunction "L_10") (pintype "unspecified"))
    )
    (net (code "214") (name "unconnected-(U12-VSS-Pad8)") (class "Default")
      (node (ref "U12") (pin "8") (pinfunction "VSS_8") (pintype "unspecified"))
    )
    (net (code "215") (name "unconnected-(U13-(A&gt;B)OUT-Pad13)") (class "Default")
      (node (ref "U13") (pin "13") (pinfunction "(A&gt;B)OUT_13") (pintype "unspecified"))
    )
    (net (code "216") (name "unconnected-(U13-(A&lt;B)OUT-Pad12)") (class "Default")
      (node (ref "U13") (pin "12") (pinfunction "(A&lt;B)OUT_12") (pintype "unspecified"))
    )
    (net (code "217") (name "unconnected-(U13-VSS-Pad8)") (class "Default")
      (node (ref "U13") (pin "8") (pinfunction "VSS_8") (pintype "unspecified"))
    )
    (net (code "218") (name "unconnected-(U15-(A&gt;B)OUT-Pad13)") (class "Default")
      (node (ref "U15") (pin "13") (pinfunction "(A&gt;B)OUT_13") (pintype "unspecified"))
    )
    (net (code "219") (name "unconnected-(U15-(A&lt;B)OUT-Pad12)") (class "Default")
      (node (ref "U15") (pin "12") (pinfunction "(A&lt;B)OUT_12") (pintype "unspecified"))
    )
    (net (code "220") (name "unconnected-(U17-3A-Pad9)") (class "Default")
      (node (ref "U17") (pin "9") (pinfunction "3A_9") (pintype "unspecified"))
    )
    (net (code "221") (name "unconnected-(U17-3B-Pad10)") (class "Default")
      (node (ref "U17") (pin "10") (pinfunction "3B_10") (pintype "unspecified"))
    )
    (net (code "222") (name "unconnected-(U17-3Y-Pad8)") (class "Default")
      (node (ref "U17") (pin "8") (pinfunction "3Y_8") (pintype "unspecified"))
    )
    (net (code "223") (name "unconnected-(U18-A-Pad3)") (class "Default")
      (node (ref "U18") (pin "3") (pinfunction "A_3") (pintype "unspecified"))
    )
    (net (code "224") (name "unconnected-(U18-B-Pad4)") (class "Default")
      (node (ref "U18") (pin "4") (pinfunction "B_4") (pintype "unspecified"))
    )
    (net (code "225") (name "unconnected-(U18-C-Pad5)") (class "Default")
      (node (ref "U18") (pin "5") (pinfunction "C_5") (pintype "unspecified"))
    )
    (net (code "226") (name "unconnected-(U18-D-Pad6)") (class "Default")
      (node (ref "U18") (pin "6") (pinfunction "D_6") (pintype "unspecified"))
    )
    (net (code "227") (name "unconnected-(U18-RCO-Pad15)") (class "Default")
      (node (ref "U18") (pin "15") (pinfunction "RCO_15") (pintype "unspecified"))
    )
    (net (code "228") (name "unconnected-(U19-A-Pad3)") (class "Default")
      (node (ref "U19") (pin "3") (pinfunction "A_3") (pintype "unspecified"))
    )
    (net (code "229") (name "unconnected-(U19-B-Pad4)") (class "Default")
      (node (ref "U19") (pin "4") (pinfunction "B_4") (pintype "unspecified"))
    )
    (net (code "230") (name "unconnected-(U19-C-Pad5)") (class "Default")
      (node (ref "U19") (pin "5") (pinfunction "C_5") (pintype "unspecified"))
    )
    (net (code "231") (name "unconnected-(U19-D-Pad6)") (class "Default")
      (node (ref "U19") (pin "6") (pinfunction "D_6") (pintype "unspecified"))
    )
    (net (code "232") (name "unconnected-(U19-RCO-Pad15)") (class "Default")
      (node (ref "U19") (pin "15") (pinfunction "RCO_15") (pintype "unspecified"))
    )
    (net (code "233") (name "unconnected-(U20-A-Pad3)") (class "Default")
      (node (ref "U20") (pin "3") (pinfunction "A_3") (pintype "unspecified"))
    )
    (net (code "234") (name "unconnected-(U20-B-Pad4)") (class "Default")
      (node (ref "U20") (pin "4") (pinfunction "B_4") (pintype "unspecified"))
    )
    (net (code "235") (name "unconnected-(U20-C-Pad5)") (class "Default")
      (node (ref "U20") (pin "5") (pinfunction "C_5") (pintype "unspecified"))
    )
    (net (code "236") (name "unconnected-(U20-D-Pad6)") (class "Default")
      (node (ref "U20") (pin "6") (pinfunction "D_6") (pintype "unspecified"))
    )
    (net (code "237") (name "unconnected-(U22-2A-Pad4)") (class "Default")
      (node (ref "U22") (pin "4") (pinfunction "2A_4") (pintype "unspecified"))
    )
    (net (code "238") (name "unconnected-(U22-2B-Pad5)") (class "Default")
      (node (ref "U22") (pin "5") (pinfunction "2B_5") (pintype "unspecified"))
    )
    (net (code "239") (name "unconnected-(U22-2Y-Pad6)") (class "Default")
      (node (ref "U22") (pin "6") (pinfunction "2Y_6") (pintype "unspecified"))
    )
    (net (code "240") (name "unconnected-(U22-3A-Pad9)") (class "Default")
      (node (ref "U22") (pin "9") (pinfunction "3A_9") (pintype "unspecified"))
    )
    (net (code "241") (name "unconnected-(U22-3B-Pad10)") (class "Default")
      (node (ref "U22") (pin "10") (pinfunction "3B_10") (pintype "unspecified"))
    )
    (net (code "242") (name "unconnected-(U22-3Y-Pad8)") (class "Default")
      (node (ref "U22") (pin "8") (pinfunction "3Y_8") (pintype "unspecified"))
    )
    (net (code "243") (name "unconnected-(U23-2A-Pad3)") (class "Default")
      (node (ref "U23") (pin "3") (pinfunction "2A_3") (pintype "unspecified"))
    )
    (net (code "244") (name "unconnected-(U23-2Y-Pad4)") (class "Default")
      (node (ref "U23") (pin "4") (pinfunction "2Y_4") (pintype "unspecified"))
    )
    (net (code "245") (name "unconnected-(U23-4A-Pad9)") (class "Default")
      (node (ref "U23") (pin "9") (pinfunction "4A_9") (pintype "unspecified"))
    )
    (net (code "246") (name "unconnected-(U23-4Y-Pad8)") (class "Default")
      (node (ref "U23") (pin "8") (pinfunction "4Y_8") (pintype "unspecified"))
    )
    (net (code "247") (name "unconnected-(U23-5A-Pad11)") (class "Default")
      (node (ref "U23") (pin "11") (pinfunction "5A_11") (pintype "unspecified"))
    )
    (net (code "248") (name "unconnected-(U23-5Y-Pad10)") (class "Default")
      (node (ref "U23") (pin "10") (pinfunction "5Y_10") (pintype "unspecified"))
    )
    (net (code "249") (name "unconnected-(U23-6A-Pad13)") (class "Default")
      (node (ref "U23") (pin "13") (pinfunction "6A_13") (pintype "unspecified"))
    )
    (net (code "250") (name "unconnected-(U23-6Y-Pad12)") (class "Default")
      (node (ref "U23") (pin "12") (pinfunction "6Y_12") (pintype "unspecified"))
    )
  )
)
